# S7G7_footprint_simplified_w_ethernet_Pow.net
KiCad netlist of a schematic drawn in EAGLE
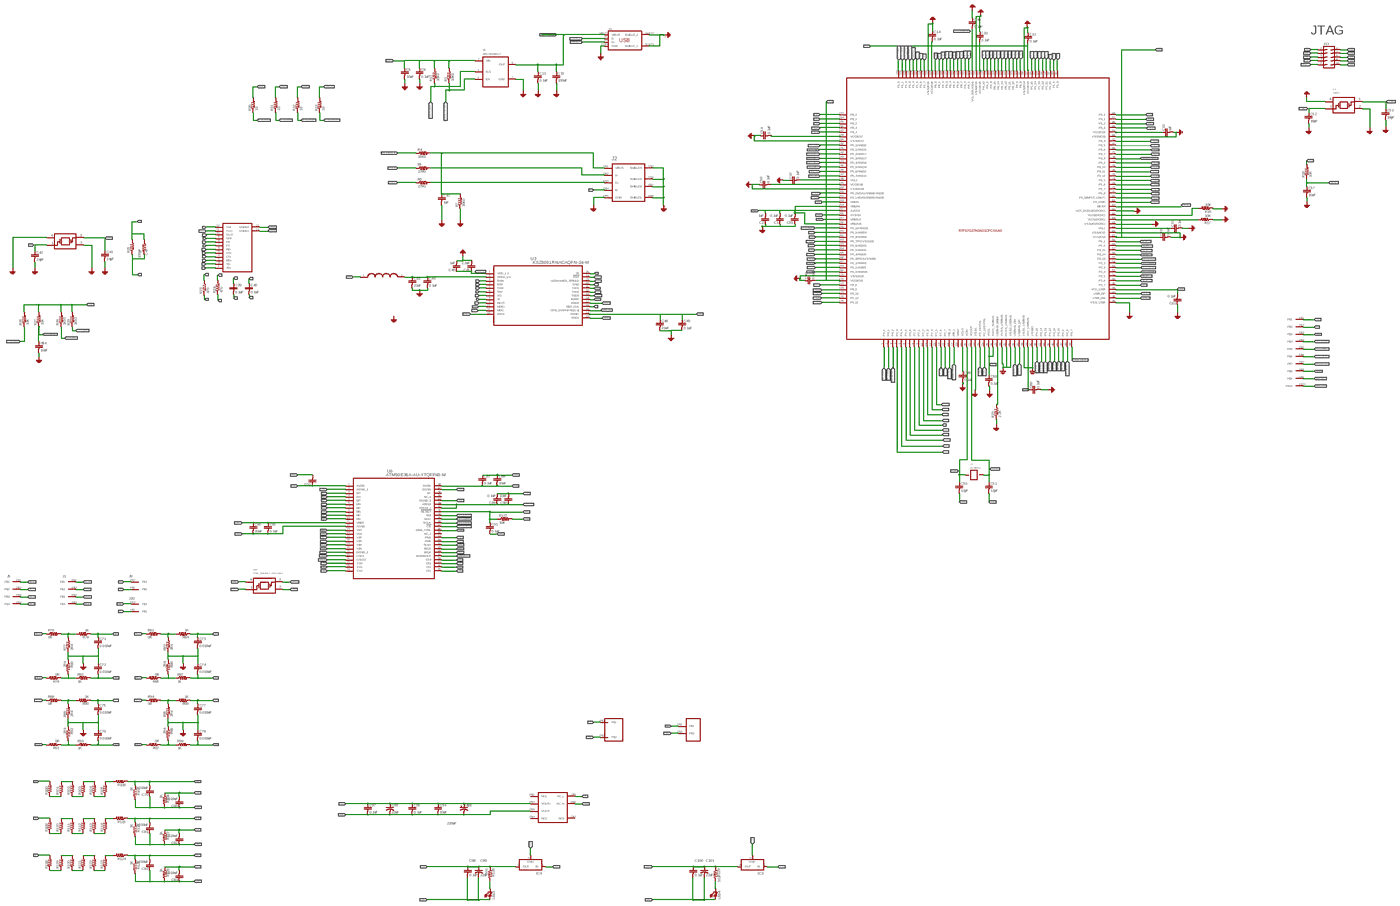
[diagram p0: schematic, sheet 1, overview]
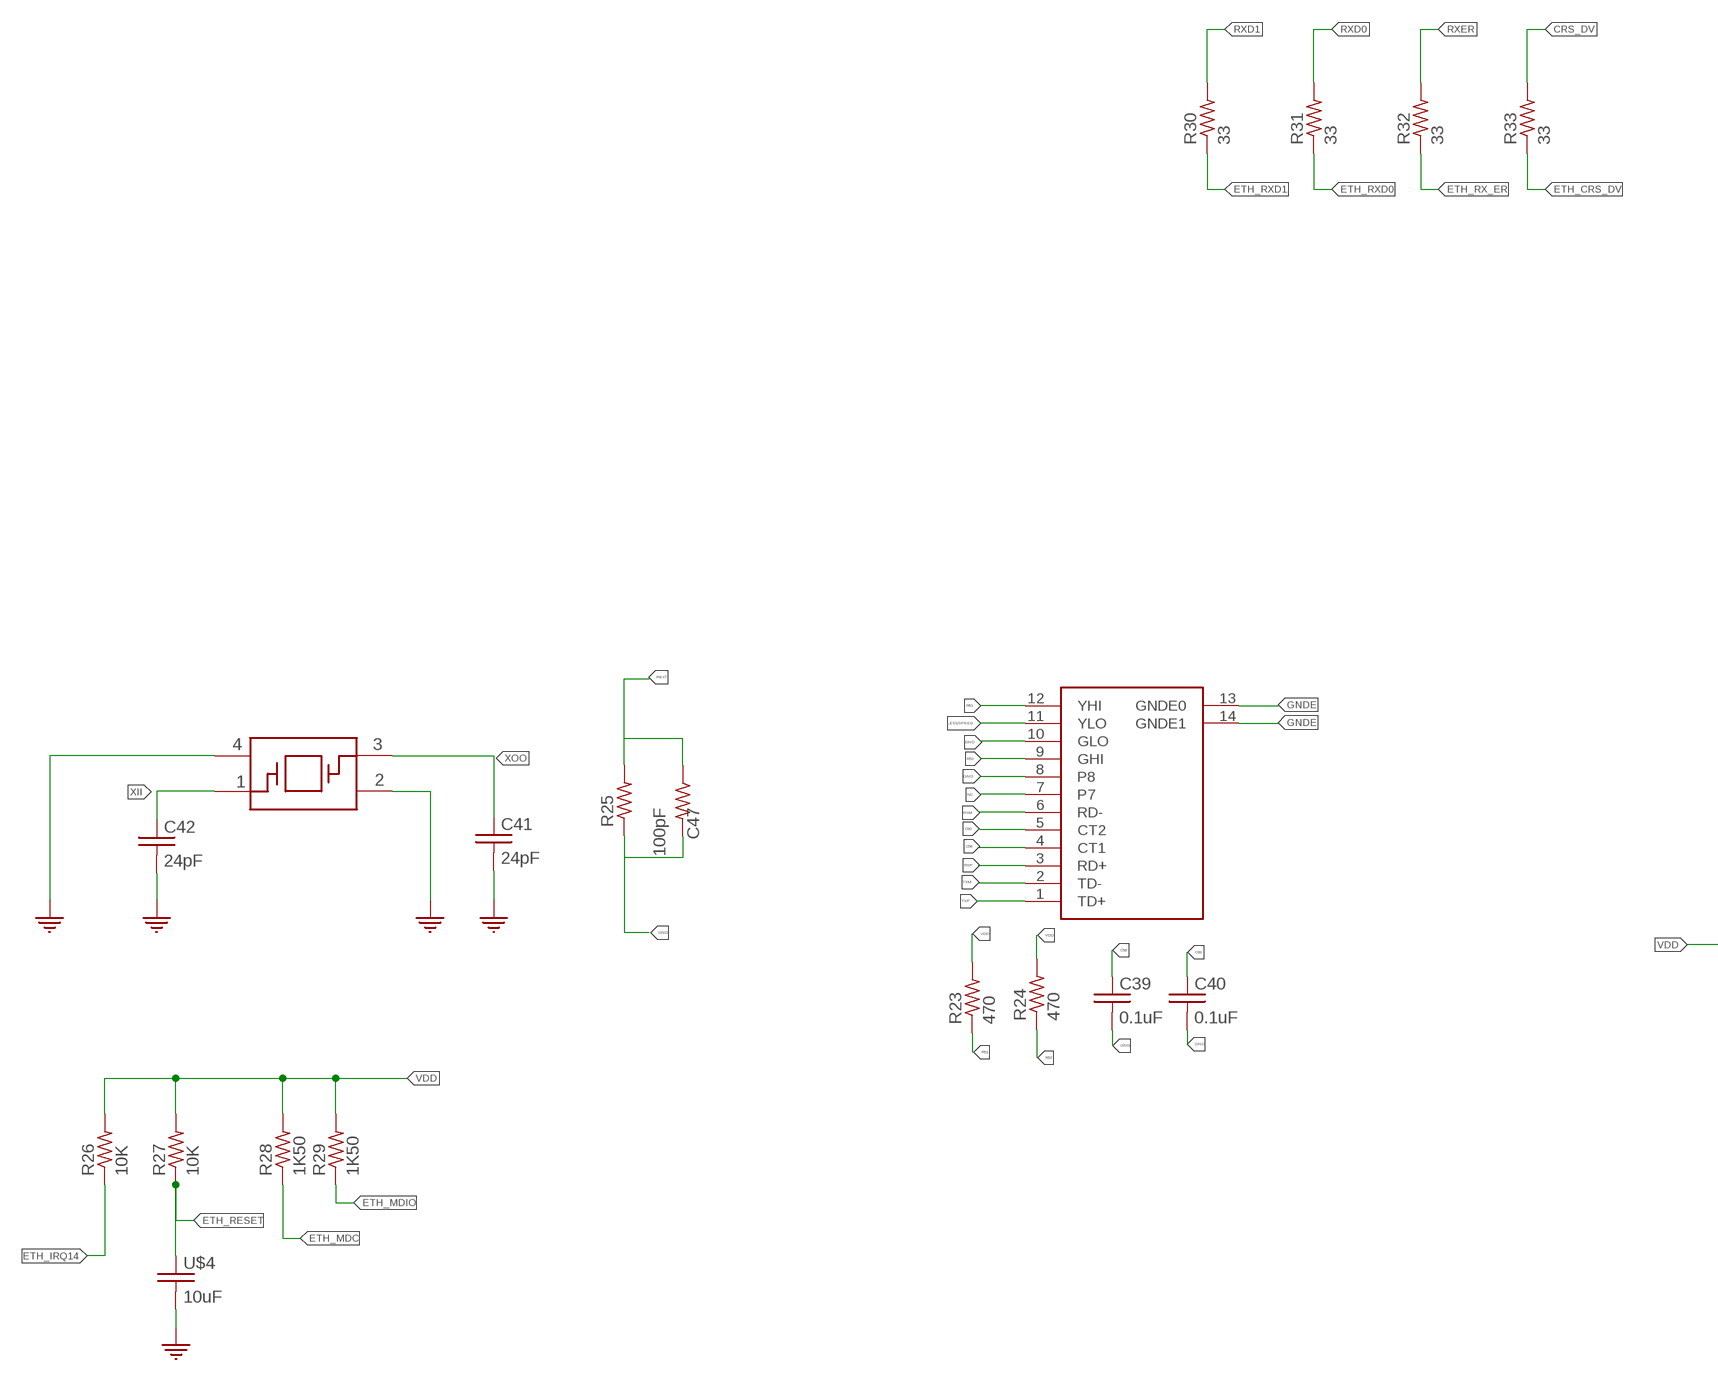
[diagram p1: schematic, sheet 1, part 1 of 6]
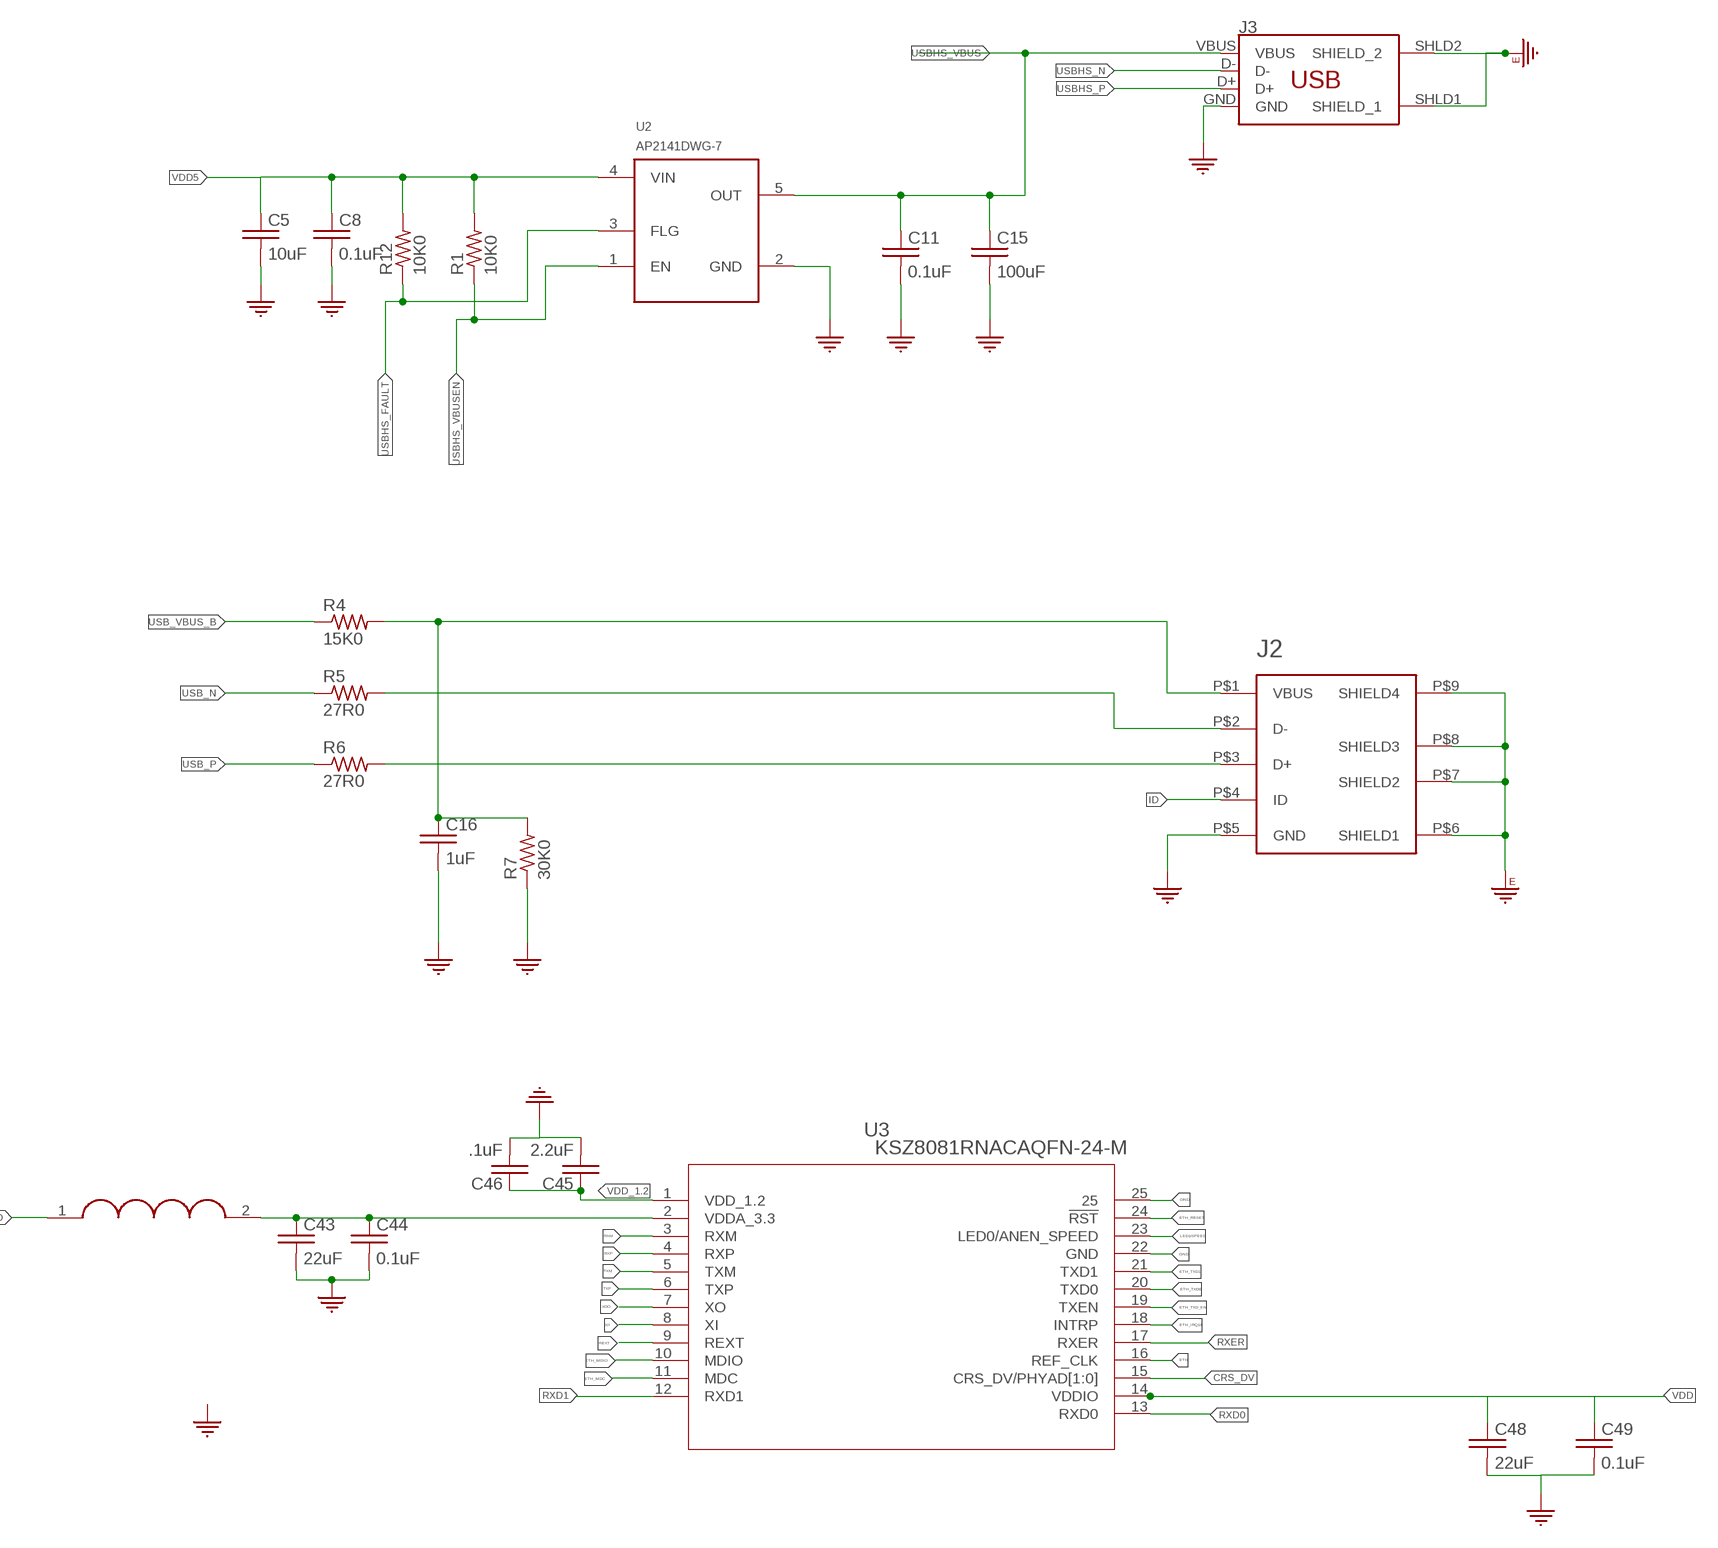
[diagram p2: schematic, sheet 1, part 2 of 6]
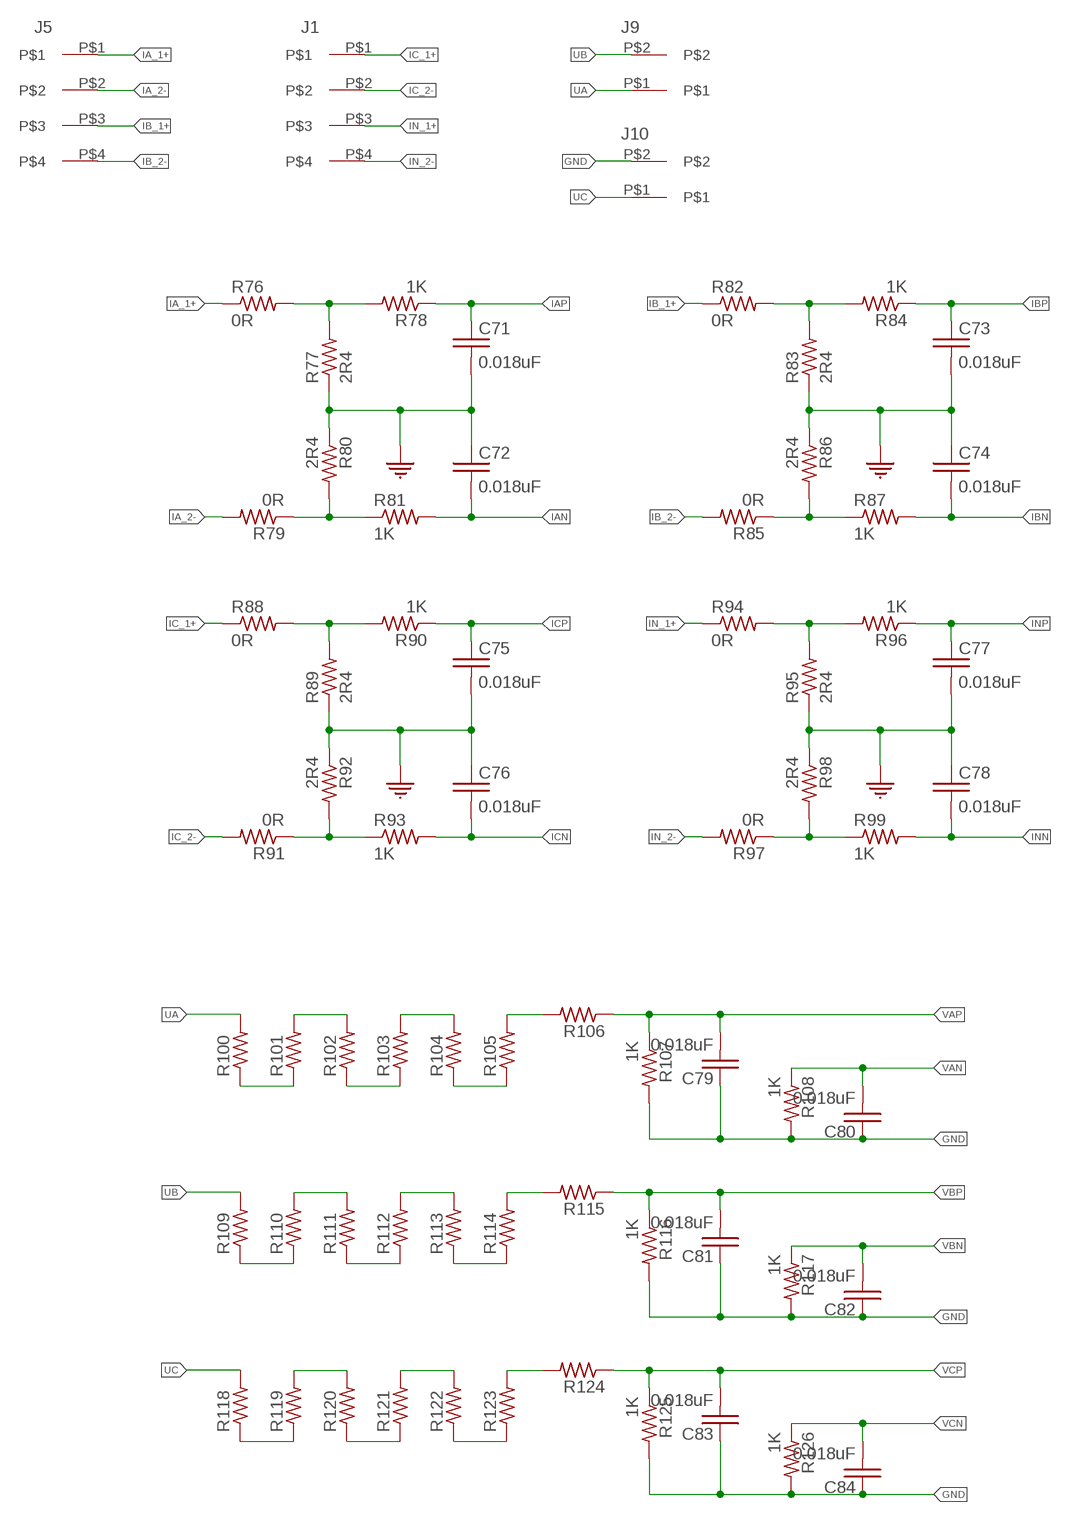
[diagram p3: schematic, sheet 1, part 3 of 6]
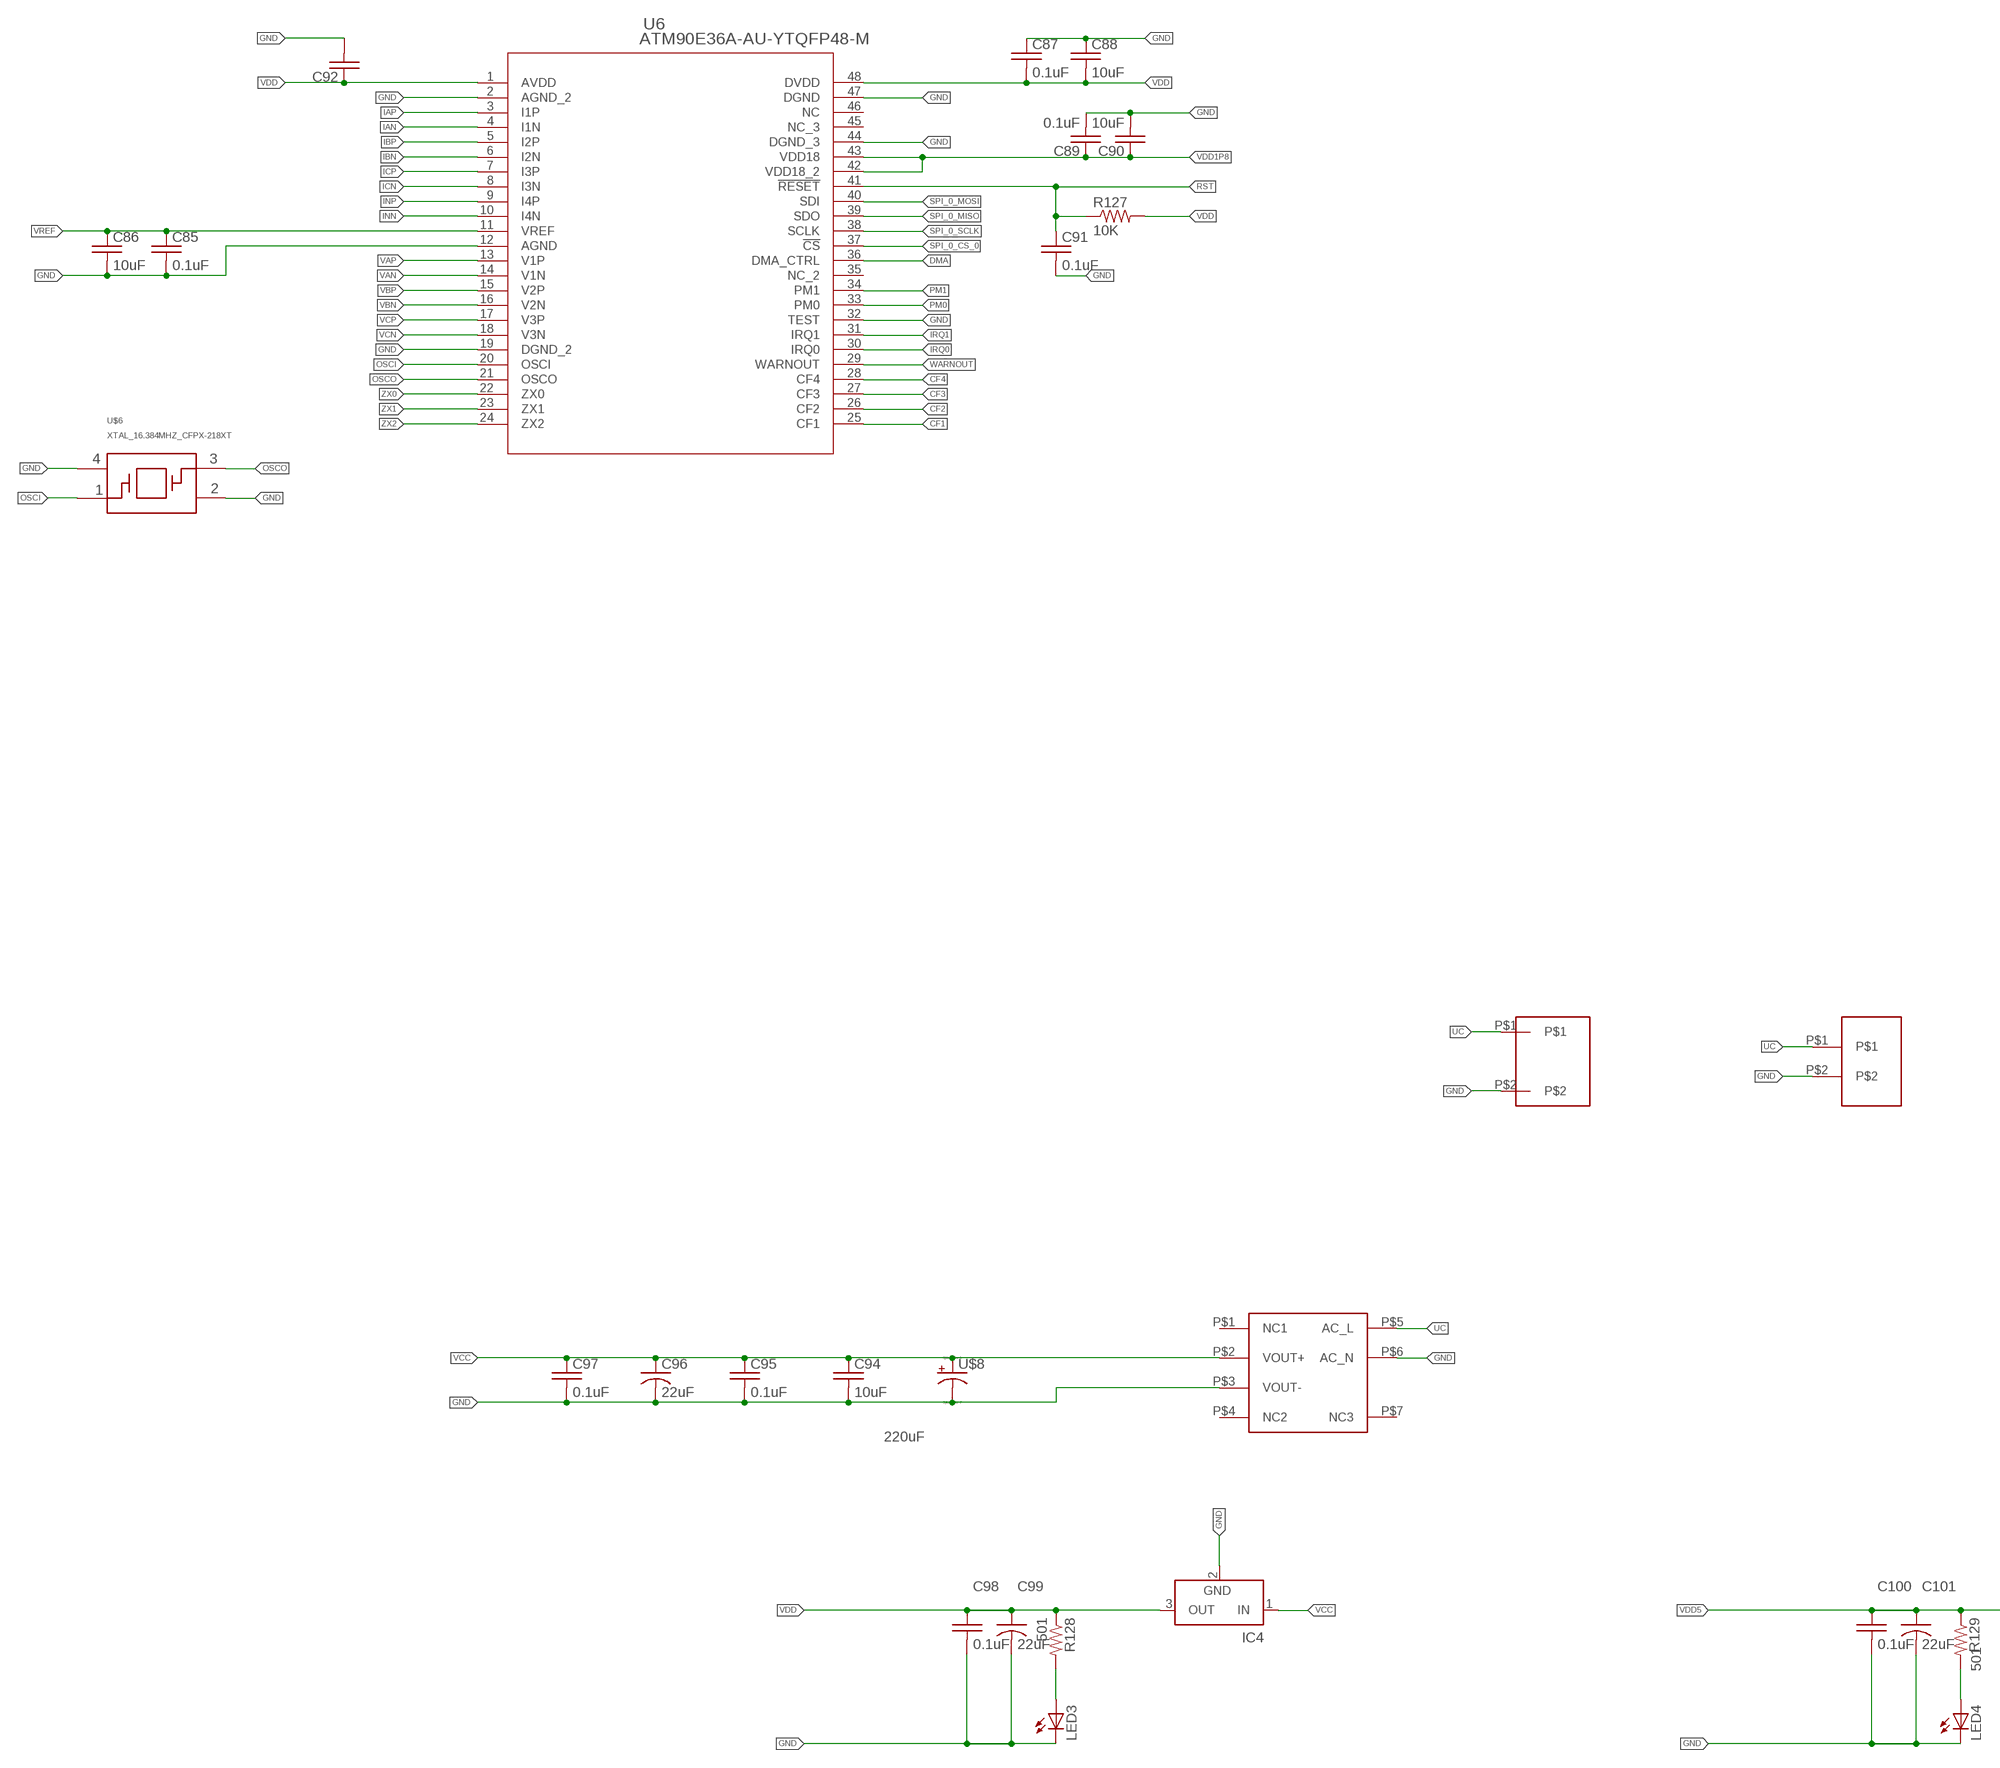
[diagram p4: schematic, sheet 1, part 4 of 6]
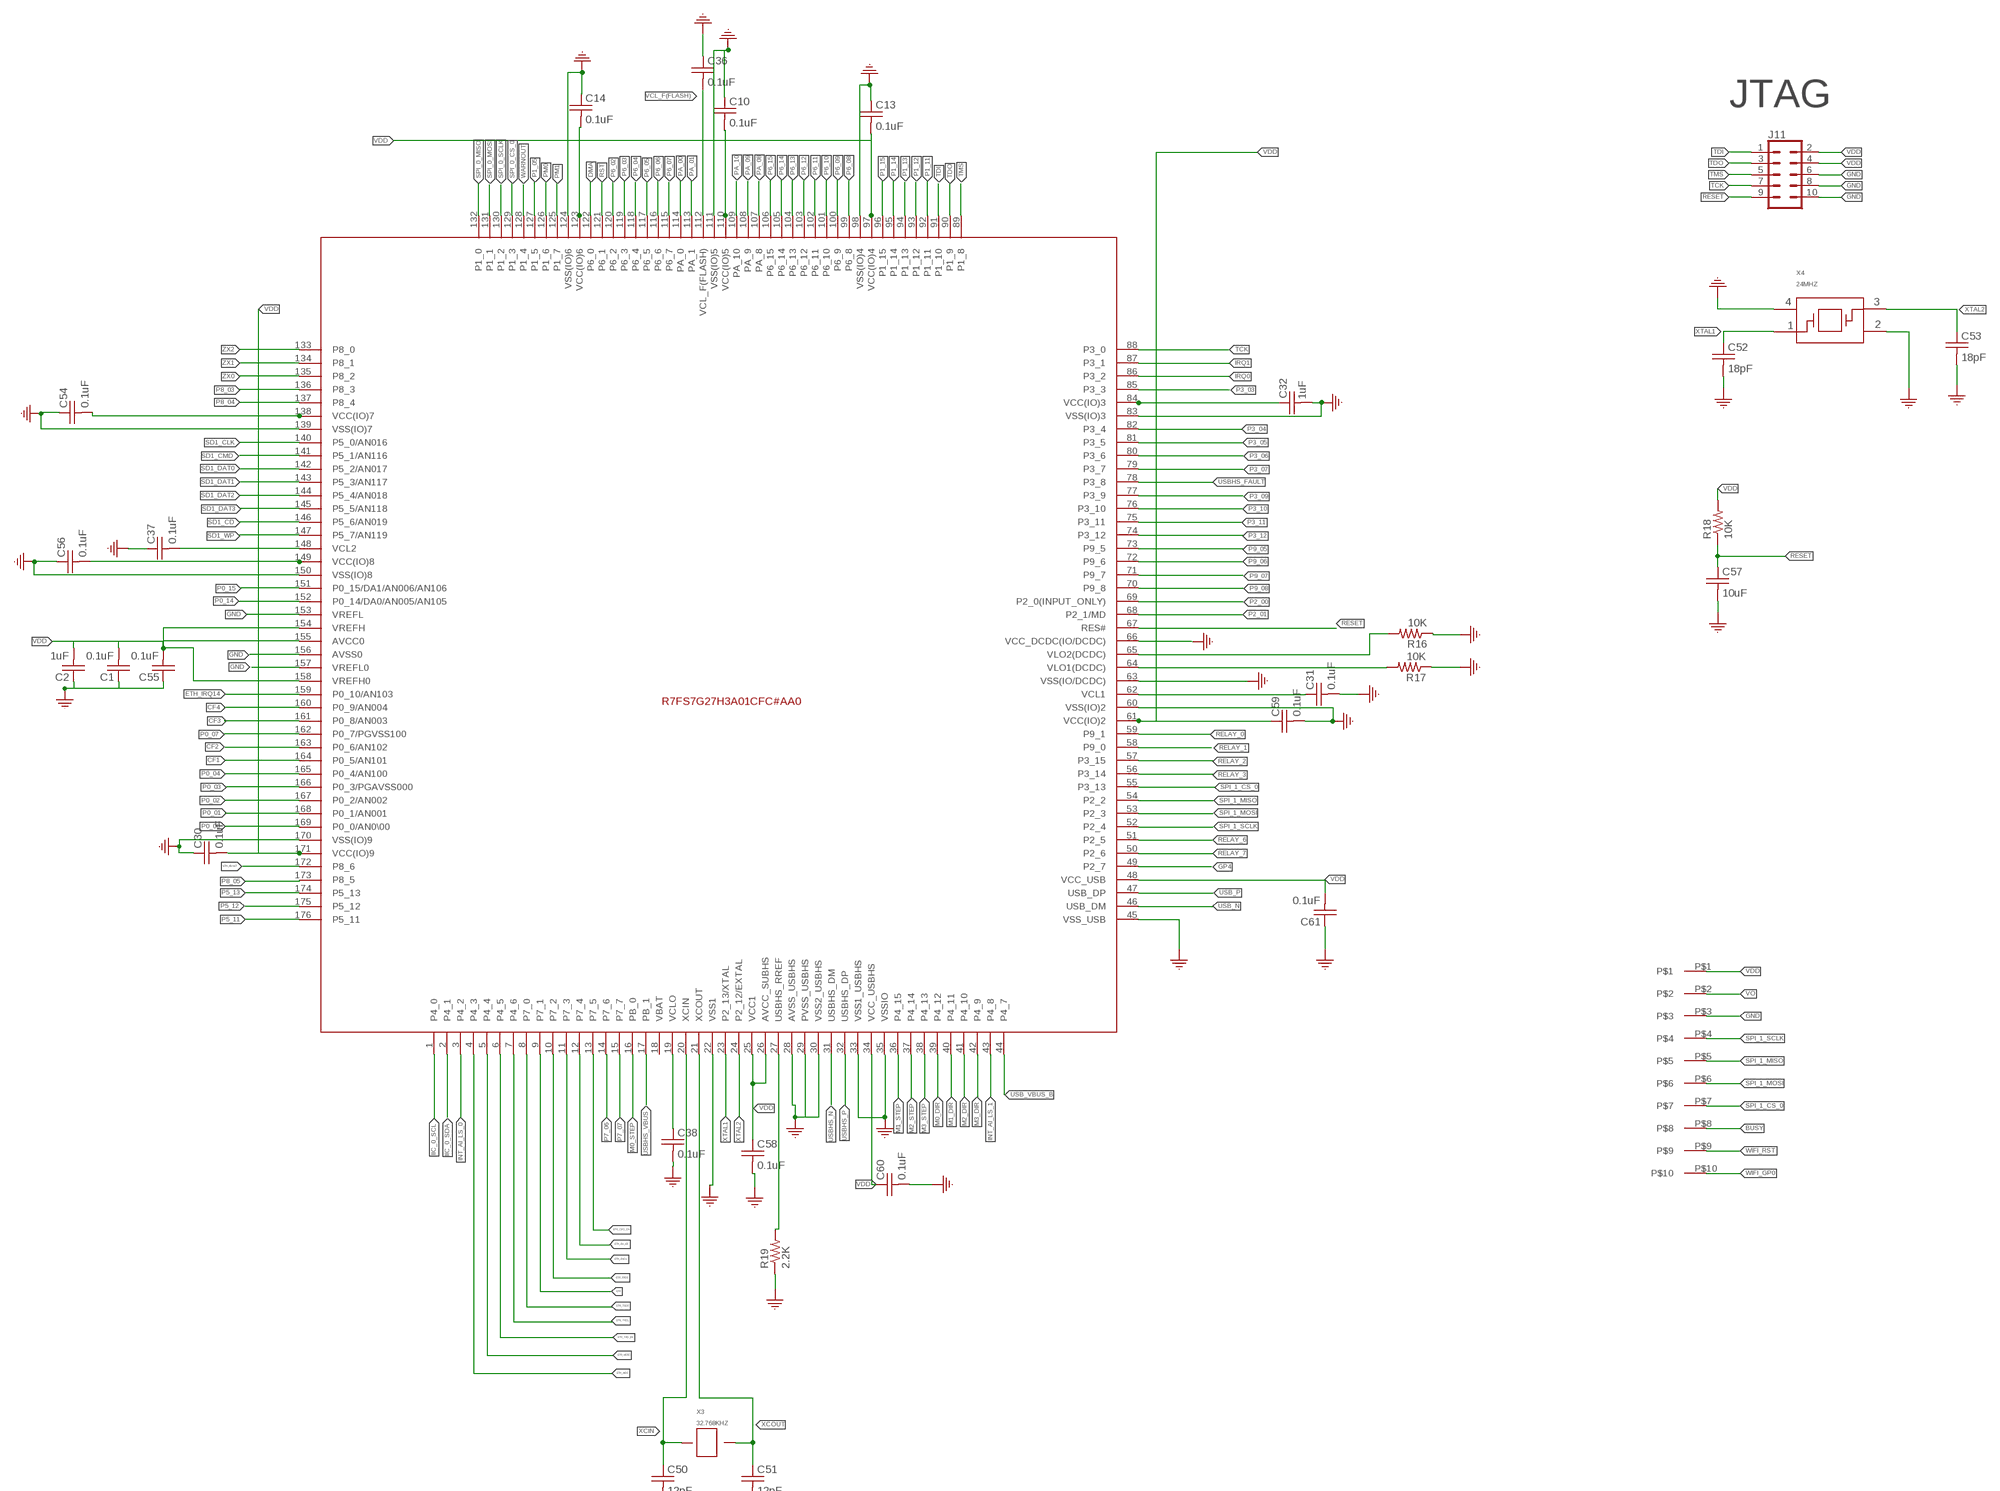
[diagram p5: schematic, sheet 1, part 5 of 6]
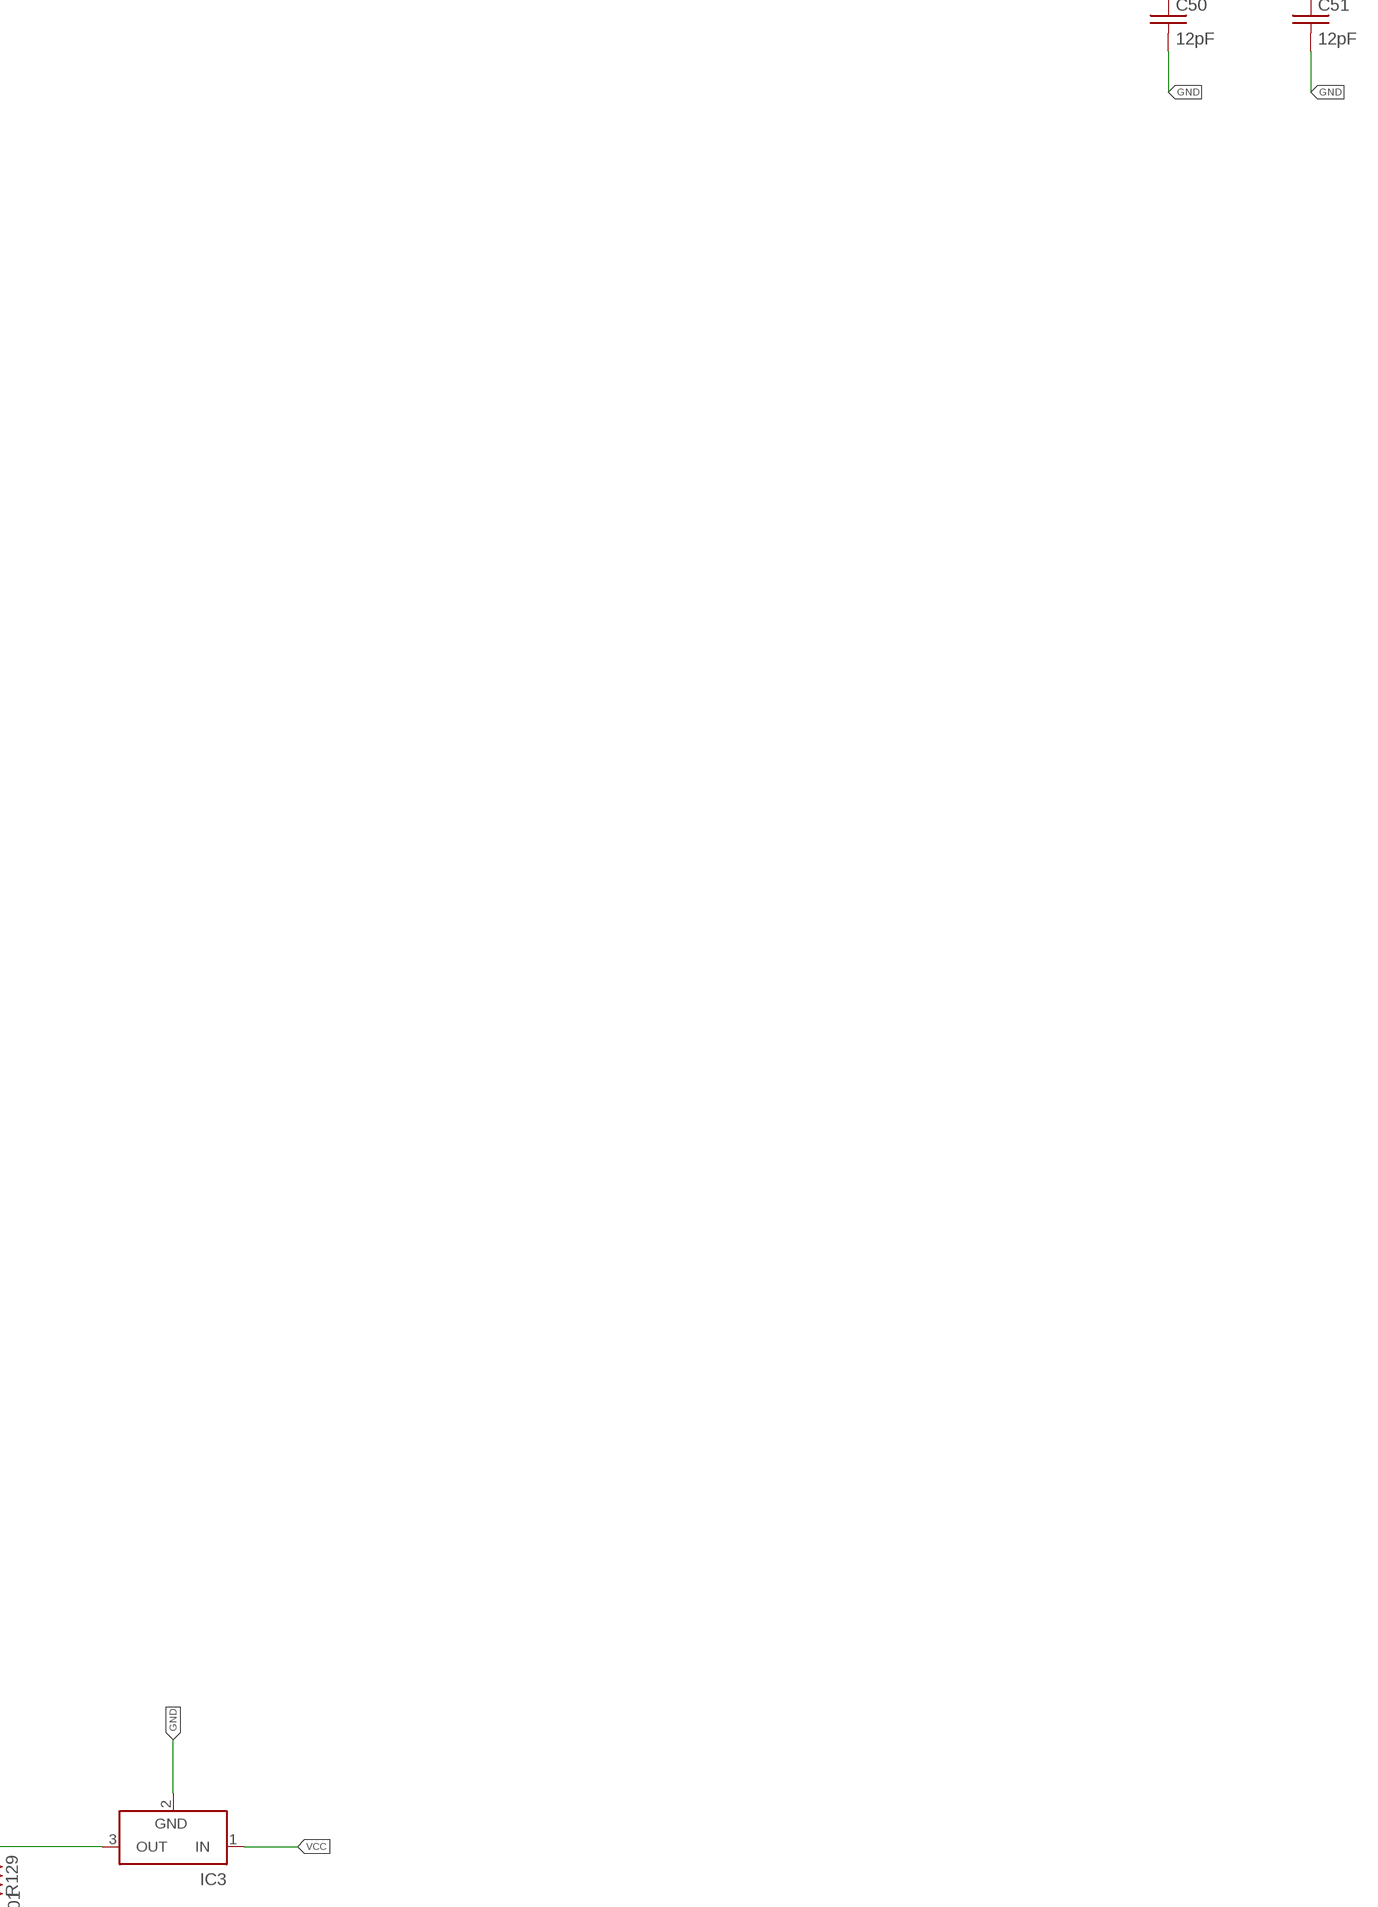
[diagram p6: schematic, sheet 1, part 6 of 6]

(export (version "E")
  (design (tool "Eeschema 10.0.6"))
  (components
    (comp (ref "C1")
      (value "0.1uF")
      (footprint "eagle-import:0402")
      (libsource (lib "eagle-import") (part "C_0402"))
    )
    (comp (ref "C2")
      (value "1uF")
      (footprint "eagle-import:0402")
      (libsource (lib "eagle-import") (part "C_0402"))
    )
    (comp (ref "C5")
      (value "10uF")
      (footprint "eagle-import:0402")
      (libsource (lib "eagle-import") (part "C_0402"))
    )
    (comp (ref "C8")
      (value "0.1uF")
      (footprint "eagle-import:0402")
      (libsource (lib "eagle-import") (part "C_0402"))
    )
    (comp (ref "C10")
      (value "0.1uF")
      (footprint "eagle-import:0402")
      (libsource (lib "eagle-import") (part "C_0402"))
    )
    (comp (ref "C11")
      (value "0.1uF")
      (footprint "eagle-import:0402")
      (libsource (lib "eagle-import") (part "C_0402"))
    )
    (comp (ref "C13")
      (value "0.1uF")
      (footprint "eagle-import:0402")
      (libsource (lib "eagle-import") (part "C_0402"))
    )
    (comp (ref "C14")
      (value "0.1uF")
      (footprint "eagle-import:0402")
      (libsource (lib "eagle-import") (part "C_0402"))
    )
    (comp (ref "C15")
      (value "100uF")
      (footprint "eagle-import:C1210")
      (libsource (lib "eagle-import") (part "C_1210"))
    )
    (comp (ref "C16")
      (value "1uF")
      (footprint "eagle-import:0402")
      (libsource (lib "eagle-import") (part "C_0402"))
    )
    (comp (ref "C30")
      (value "0.1uF")
      (footprint "eagle-import:0402")
      (libsource (lib "eagle-import") (part "C_0402"))
    )
    (comp (ref "C31")
      (value "0.1uF")
      (footprint "eagle-import:0402")
      (libsource (lib "eagle-import") (part "C_0402"))
    )
    (comp (ref "C32")
      (value "1uF")
      (footprint "eagle-import:0402")
      (libsource (lib "eagle-import") (part "C_0402"))
    )
    (comp (ref "C36")
      (value "0.1uF")
      (footprint "eagle-import:0402")
      (libsource (lib "eagle-import") (part "C_0402"))
    )
    (comp (ref "C37")
      (value "0.1uF")
      (footprint "eagle-import:0402")
      (libsource (lib "eagle-import") (part "C_0402"))
    )
    (comp (ref "C38")
      (value "0.1uF")
      (footprint "eagle-import:0402")
      (libsource (lib "eagle-import") (part "C_0402"))
    )
    (comp (ref "C39")
      (value "0.1uF")
      (footprint "eagle-import:0402")
      (libsource (lib "eagle-import") (part "C_0402"))
    )
    (comp (ref "C40")
      (value "0.1uF")
      (footprint "eagle-import:0402")
      (libsource (lib "eagle-import") (part "C_0402"))
    )
    (comp (ref "C41")
      (value "24pF")
      (footprint "eagle-import:0402")
      (libsource (lib "eagle-import") (part "C_0402"))
    )
    (comp (ref "C42")
      (value "24pF")
      (footprint "eagle-import:0402")
      (libsource (lib "eagle-import") (part "C_0402"))
    )
    (comp (ref "C43")
      (value "22uF")
      (footprint "eagle-import:0603")
      (libsource (lib "eagle-import") (part "C_0603"))
    )
    (comp (ref "C44")
      (value "0.1uF")
      (footprint "eagle-import:0402")
      (libsource (lib "eagle-import") (part "C_0402"))
    )
    (comp (ref "C45")
      (value "2.2uF")
      (footprint "eagle-import:0402")
      (libsource (lib "eagle-import") (part "C_0402"))
    )
    (comp (ref "C46")
      (value ".1uF")
      (footprint "eagle-import:0402")
      (libsource (lib "eagle-import") (part "C_0402"))
    )
    (comp (ref "C47")
      (value "100pF")
      (footprint "eagle-import:0402")
      (libsource (lib "eagle-import") (part "R_0402"))
    )
    (comp (ref "C48")
      (value "22uF")
      (footprint "eagle-import:0603")
      (libsource (lib "eagle-import") (part "C_0603"))
    )
    (comp (ref "C49")
      (value "0.1uF")
      (footprint "eagle-import:0402")
      (libsource (lib "eagle-import") (part "C_0402"))
    )
    (comp (ref "C50")
      (value "12pF")
      (footprint "eagle-import:0402")
      (libsource (lib "eagle-import") (part "C_0402"))
    )
    (comp (ref "C51")
      (value "12pF")
      (footprint "eagle-import:0402")
      (libsource (lib "eagle-import") (part "C_0402"))
    )
    (comp (ref "C52")
      (value "18pF")
      (footprint "eagle-import:0402")
      (libsource (lib "eagle-import") (part "C_0402"))
    )
    (comp (ref "C53")
      (value "18pF")
      (footprint "eagle-import:0402")
      (libsource (lib "eagle-import") (part "C_0402"))
    )
    (comp (ref "C54")
      (value "0.1uF")
      (footprint "eagle-import:0402")
      (libsource (lib "eagle-import") (part "C_0402"))
    )
    (comp (ref "C55")
      (value "0.1uF")
      (footprint "eagle-import:0402")
      (libsource (lib "eagle-import") (part "C_0402"))
    )
    (comp (ref "C56")
      (value "0.1uF")
      (footprint "eagle-import:0402")
      (libsource (lib "eagle-import") (part "C_0402"))
    )
    (comp (ref "C57")
      (value "10uF")
      (footprint "eagle-import:0402")
      (libsource (lib "eagle-import") (part "C_0402"))
    )
    (comp (ref "C58")
      (value "0.1uF")
      (footprint "eagle-import:0402")
      (libsource (lib "eagle-import") (part "C_0402"))
    )
    (comp (ref "C59")
      (value "0.1uF")
      (footprint "eagle-import:0402")
      (libsource (lib "eagle-import") (part "C_0402"))
    )
    (comp (ref "C60")
      (value "0.1uF")
      (footprint "eagle-import:0402")
      (libsource (lib "eagle-import") (part "C_0402"))
    )
    (comp (ref "C61")
      (value "0.1uF")
      (footprint "eagle-import:0402")
      (libsource (lib "eagle-import") (part "C_0402"))
    )
    (comp (ref "C71")
      (value "0.018uF")
      (footprint "eagle-import:0402")
      (libsource (lib "eagle-import") (part "C_0402"))
    )
    (comp (ref "C72")
      (value "0.018uF")
      (footprint "eagle-import:0402")
      (libsource (lib "eagle-import") (part "C_0402"))
    )
    (comp (ref "C73")
      (value "0.018uF")
      (footprint "eagle-import:0402")
      (libsource (lib "eagle-import") (part "C_0402"))
    )
    (comp (ref "C74")
      (value "0.018uF")
      (footprint "eagle-import:0402")
      (libsource (lib "eagle-import") (part "C_0402"))
    )
    (comp (ref "C75")
      (value "0.018uF")
      (footprint "eagle-import:0402")
      (libsource (lib "eagle-import") (part "C_0402"))
    )
    (comp (ref "C76")
      (value "0.018uF")
      (footprint "eagle-import:0402")
      (libsource (lib "eagle-import") (part "C_0402"))
    )
    (comp (ref "C77")
      (value "0.018uF")
      (footprint "eagle-import:0402")
      (libsource (lib "eagle-import") (part "C_0402"))
    )
    (comp (ref "C78")
      (value "0.018uF")
      (footprint "eagle-import:0402")
      (libsource (lib "eagle-import") (part "C_0402"))
    )
    (comp (ref "C79")
      (value "0.018uF")
      (footprint "eagle-import:0402")
      (libsource (lib "eagle-import") (part "C_0402"))
    )
    (comp (ref "C80")
      (value "0.018uF")
      (footprint "eagle-import:0402")
      (libsource (lib "eagle-import") (part "C_0402"))
    )
    (comp (ref "C81")
      (value "0.018uF")
      (footprint "eagle-import:0402")
      (libsource (lib "eagle-import") (part "C_0402"))
    )
    (comp (ref "C82")
      (value "0.018uF")
      (footprint "eagle-import:0402")
      (libsource (lib "eagle-import") (part "C_0402"))
    )
    (comp (ref "C83")
      (value "0.018uF")
      (footprint "eagle-import:0402")
      (libsource (lib "eagle-import") (part "C_0402"))
    )
    (comp (ref "C84")
      (value "0.018uF")
      (footprint "eagle-import:0402")
      (libsource (lib "eagle-import") (part "C_0402"))
    )
    (comp (ref "C85")
      (value "0.1uF")
      (footprint "eagle-import:0402")
      (libsource (lib "eagle-import") (part "C_0402"))
    )
    (comp (ref "C86")
      (value "10uF")
      (footprint "eagle-import:0402")
      (libsource (lib "eagle-import") (part "C_0402"))
    )
    (comp (ref "C87")
      (value "0.1uF")
      (footprint "eagle-import:0402")
      (libsource (lib "eagle-import") (part "C_0402"))
    )
    (comp (ref "C88")
      (value "10uF")
      (footprint "eagle-import:0402")
      (libsource (lib "eagle-import") (part "C_0402"))
    )
    (comp (ref "C89")
      (value "0.1uF")
      (footprint "eagle-import:0402")
      (libsource (lib "eagle-import") (part "C_0402"))
    )
    (comp (ref "C90")
      (value "10uF")
      (footprint "eagle-import:0402")
      (libsource (lib "eagle-import") (part "C_0402"))
    )
    (comp (ref "C91")
      (value "0.1uF")
      (footprint "eagle-import:0402")
      (libsource (lib "eagle-import") (part "C_0402"))
    )
    (comp (ref "C92")
      (value "C_0402")
      (footprint "eagle-import:0402")
      (libsource (lib "eagle-import") (part "C_0402"))
    )
    (comp (ref "C93")
      (value "CAP_THIN_FILM_TDK_32922CAP")
      (footprint "eagle-import:CAP_THIN_FILM_32922")
      (libsource (lib "eagle-import") (part "CAP_THIN_FILM_TDK_32922CAP"))
    )
    (comp (ref "C94")
      (value "10uF")
      (footprint "eagle-import:0402")
      (libsource (lib "eagle-import") (part "C_0402"))
    )
    (comp (ref "C95")
      (value "0.1uF")
      (footprint "eagle-import:0402")
      (libsource (lib "eagle-import") (part "C_0402"))
    )
    (comp (ref "C96")
      (value "22uF")
      (footprint "eagle-import:C1206")
      (libsource (lib "eagle-import") (part "C-USC1206"))
    )
    (comp (ref "C97")
      (value "0.1uF")
      (footprint "eagle-import:0402")
      (libsource (lib "eagle-import") (part "C_0402"))
    )
    (comp (ref "C98")
      (value "0.1uF")
      (footprint "eagle-import:0402")
      (libsource (lib "eagle-import") (part "C_0402"))
    )
    (comp (ref "C99")
      (value "22uF")
      (footprint "eagle-import:C1206")
      (libsource (lib "eagle-import") (part "C-USC1206"))
    )
    (comp (ref "C100")
      (value "0.1uF")
      (footprint "eagle-import:0402")
      (libsource (lib "eagle-import") (part "C_0402"))
    )
    (comp (ref "C101")
      (value "22uF")
      (footprint "eagle-import:C1206")
      (libsource (lib "eagle-import") (part "C-USC1206"))
    )
    (comp (ref "FB2/2")
      (value "FB_0805_120_OHM")
      (footprint "eagle-import:0805")
      (libsource (lib "eagle-import") (part "FB_0805_120_OHM"))
    )
    (comp (ref "IC3")
      (value "LT1129CST5")
      (footprint "eagle-import:SOT223")
      (fields (field (name "MPN") "LT1129CST-5#PBF"))
      (libsource (lib "eagle-import") (part "LT1129CST5"))
    )
    (comp (ref "IC4")
      (value "LT1129CST3")
      (footprint "eagle-import:SOT223")
      (fields (field (name "MPN") "LT1129CST-5#PBF"))
      (libsource (lib "eagle-import") (part "LT1129CST3"))
    )
    (comp (ref "J1")
      (value "3.81MM_1_X_4_RT_ANGLE_PLUG_HEADER")
      (footprint "eagle-import:1X4_3.81MM_PITCH")
      (libsource (lib "eagle-import") (part "3.81MM_1_X_4_RT_ANGLE_PLUG_HEADER"))
    )
    (comp (ref "J2")
      (value "USB_MICRO-B")
      (footprint "eagle-import:USB_MICRO-B")
      (libsource (lib "eagle-import") (part "USB_MICRO-B"))
    )
    (comp (ref "J3")
      (value "USB_A")
      (footprint "eagle-import:USB_A_SMT")
      (libsource (lib "eagle-import") (part "USB_A"))
    )
    (comp (ref "J4")
      (value "RJ45_WITH_ELEC")
      (footprint "eagle-import:RJ45_TH_ELEC")
      (libsource (lib "eagle-import") (part "RJ45_WITH_ELEC"))
    )
    (comp (ref "J5")
      (value "3.81MM_1_X_4_RT_ANGLE_PLUG_HEADER")
      (footprint "eagle-import:1X4_3.81MM_PITCH")
      (libsource (lib "eagle-import") (part "3.81MM_1_X_4_RT_ANGLE_PLUG_HEADER"))
    )
    (comp (ref "J9")
      (value "3.81MM_1_X_2_RT_ANGLE_PLUG_HEADER")
      (footprint "eagle-import:2_3.81MM_PITCH")
      (libsource (lib "eagle-import") (part "3.81MM_1_X_2_RT_ANGLE_PLUG_HEADER"))
    )
    (comp (ref "J10")
      (value "3.81MM_1_X_2_RT_ANGLE_PLUG_HEADER")
      (footprint "eagle-import:2_3.81MM_PITCH")
      (libsource (lib "eagle-import") (part "3.81MM_1_X_2_RT_ANGLE_PLUG_HEADER"))
    )
    (comp (ref "J11")
      (value "CONN_05X2PTH")
      (footprint "eagle-import:2X5")
      (libsource (lib "eagle-import") (part "CONN_05X2PTH"))
    )
    (comp (ref "LED3")
      (value "LED_0805_GREEN")
      (footprint "eagle-import:LED_0805_GREEN")
      (libsource (lib "eagle-import") (part "LED_0805_GREEN"))
    )
    (comp (ref "LED4")
      (value "LED_0805_GREEN")
      (footprint "eagle-import:LED_0805_GREEN")
      (libsource (lib "eagle-import") (part "LED_0805_GREEN"))
    )
    (comp (ref "R1")
      (value "10K0")
      (footprint "eagle-import:0402")
      (libsource (lib "eagle-import") (part "R_0402"))
    )
    (comp (ref "R4")
      (value "15K0")
      (footprint "eagle-import:0402")
      (libsource (lib "eagle-import") (part "R_0402"))
    )
    (comp (ref "R5")
      (value "27R0")
      (footprint "eagle-import:0402")
      (libsource (lib "eagle-import") (part "R_0402"))
    )
    (comp (ref "R6")
      (value "27R0")
      (footprint "eagle-import:0402")
      (libsource (lib "eagle-import") (part "R_0402"))
    )
    (comp (ref "R7")
      (value "30K0")
      (footprint "eagle-import:0402")
      (libsource (lib "eagle-import") (part "R_0402"))
    )
    (comp (ref "R12")
      (value "10K0")
      (footprint "eagle-import:0402")
      (libsource (lib "eagle-import") (part "R_0402"))
    )
    (comp (ref "R16")
      (value "10K")
      (footprint "eagle-import:0402")
      (libsource (lib "eagle-import") (part "R_0402"))
    )
    (comp (ref "R17")
      (value "10K")
      (footprint "eagle-import:0402")
      (libsource (lib "eagle-import") (part "R_0402"))
    )
    (comp (ref "R18")
      (value "10K")
      (footprint "eagle-import:0402")
      (libsource (lib "eagle-import") (part "R_0402"))
    )
    (comp (ref "R19")
      (value "2.2K")
      (footprint "eagle-import:0402")
      (libsource (lib "eagle-import") (part "R_0402"))
    )
    (comp (ref "R23")
      (value "470")
      (footprint "eagle-import:0402")
      (libsource (lib "eagle-import") (part "R_0402"))
    )
    (comp (ref "R24")
      (value "470")
      (footprint "eagle-import:0402")
      (libsource (lib "eagle-import") (part "R_0402"))
    )
    (comp (ref "R25")
      (value "6k49")
      (footprint "eagle-import:0402")
      (libsource (lib "eagle-import") (part "R_0402"))
    )
    (comp (ref "R26")
      (value "10K")
      (footprint "eagle-import:0402")
      (libsource (lib "eagle-import") (part "R_0402"))
    )
    (comp (ref "R27")
      (value "10K")
      (footprint "eagle-import:0402")
      (libsource (lib "eagle-import") (part "R_0402"))
    )
    (comp (ref "R28")
      (value "1K50")
      (footprint "eagle-import:0402")
      (libsource (lib "eagle-import") (part "R_0402"))
    )
    (comp (ref "R29")
      (value "1K50")
      (footprint "eagle-import:0402")
      (libsource (lib "eagle-import") (part "R_0402"))
    )
    (comp (ref "R30")
      (value "33")
      (footprint "eagle-import:0402")
      (libsource (lib "eagle-import") (part "R_0402"))
    )
    (comp (ref "R31")
      (value "33")
      (footprint "eagle-import:0402")
      (libsource (lib "eagle-import") (part "R_0402"))
    )
    (comp (ref "R32")
      (value "33")
      (footprint "eagle-import:0402")
      (libsource (lib "eagle-import") (part "R_0402"))
    )
    (comp (ref "R33")
      (value "33")
      (footprint "eagle-import:0402")
      (libsource (lib "eagle-import") (part "R_0402"))
    )
    (comp (ref "R76")
      (value "0R")
      (footprint "eagle-import:0402")
      (libsource (lib "eagle-import") (part "R_0402"))
    )
    (comp (ref "R77")
      (value "2R4")
      (footprint "eagle-import:0402")
      (libsource (lib "eagle-import") (part "R_0402"))
    )
    (comp (ref "R78")
      (value "1K")
      (footprint "eagle-import:0402")
      (libsource (lib "eagle-import") (part "R_0402"))
    )
    (comp (ref "R79")
      (value "0R")
      (footprint "eagle-import:0402")
      (libsource (lib "eagle-import") (part "R_0402"))
    )
    (comp (ref "R80")
      (value "2R4")
      (footprint "eagle-import:0402")
      (libsource (lib "eagle-import") (part "R_0402"))
    )
    (comp (ref "R81")
      (value "1K")
      (footprint "eagle-import:0402")
      (libsource (lib "eagle-import") (part "R_0402"))
    )
    (comp (ref "R82")
      (value "0R")
      (footprint "eagle-import:0402")
      (libsource (lib "eagle-import") (part "R_0402"))
    )
    (comp (ref "R83")
      (value "2R4")
      (footprint "eagle-import:0402")
      (libsource (lib "eagle-import") (part "R_0402"))
    )
    (comp (ref "R84")
      (value "1K")
      (footprint "eagle-import:0402")
      (libsource (lib "eagle-import") (part "R_0402"))
    )
    (comp (ref "R85")
      (value "0R")
      (footprint "eagle-import:0402")
      (libsource (lib "eagle-import") (part "R_0402"))
    )
    (comp (ref "R86")
      (value "2R4")
      (footprint "eagle-import:0402")
      (libsource (lib "eagle-import") (part "R_0402"))
    )
    (comp (ref "R87")
      (value "1K")
      (footprint "eagle-import:0402")
      (libsource (lib "eagle-import") (part "R_0402"))
    )
    (comp (ref "R88")
      (value "0R")
      (footprint "eagle-import:0402")
      (libsource (lib "eagle-import") (part "R_0402"))
    )
    (comp (ref "R89")
      (value "2R4")
      (footprint "eagle-import:0402")
      (libsource (lib "eagle-import") (part "R_0402"))
    )
    (comp (ref "R90")
      (value "1K")
      (footprint "eagle-import:0402")
      (libsource (lib "eagle-import") (part "R_0402"))
    )
    (comp (ref "R91")
      (value "0R")
      (footprint "eagle-import:0402")
      (libsource (lib "eagle-import") (part "R_0402"))
    )
    (comp (ref "R92")
      (value "2R4")
      (footprint "eagle-import:0402")
      (libsource (lib "eagle-import") (part "R_0402"))
    )
    (comp (ref "R93")
      (value "1K")
      (footprint "eagle-import:0402")
      (libsource (lib "eagle-import") (part "R_0402"))
    )
    (comp (ref "R94")
      (value "0R")
      (footprint "eagle-import:0402")
      (libsource (lib "eagle-import") (part "R_0402"))
    )
    (comp (ref "R95")
      (value "2R4")
      (footprint "eagle-import:0402")
      (libsource (lib "eagle-import") (part "R_0402"))
    )
    (comp (ref "R96")
      (value "1K")
      (footprint "eagle-import:0402")
      (libsource (lib "eagle-import") (part "R_0402"))
    )
    (comp (ref "R97")
      (value "0R")
      (footprint "eagle-import:0402")
      (libsource (lib "eagle-import") (part "R_0402"))
    )
    (comp (ref "R98")
      (value "2R4")
      (footprint "eagle-import:0402")
      (libsource (lib "eagle-import") (part "R_0402"))
    )
    (comp (ref "R99")
      (value "1K")
      (footprint "eagle-import:0402")
      (libsource (lib "eagle-import") (part "R_0402"))
    )
    (comp (ref "R100")
      (value "R_0402")
      (footprint "eagle-import:0402")
      (libsource (lib "eagle-import") (part "R_0402"))
    )
    (comp (ref "R101")
      (value "R_0402")
      (footprint "eagle-import:0402")
      (libsource (lib "eagle-import") (part "R_0402"))
    )
    (comp (ref "R102")
      (value "R_0402")
      (footprint "eagle-import:0402")
      (libsource (lib "eagle-import") (part "R_0402"))
    )
    (comp (ref "R103")
      (value "R_0402")
      (footprint "eagle-import:0402")
      (libsource (lib "eagle-import") (part "R_0402"))
    )
    (comp (ref "R104")
      (value "R_0402")
      (footprint "eagle-import:0402")
      (libsource (lib "eagle-import") (part "R_0402"))
    )
    (comp (ref "R105")
      (value "R_0402")
      (footprint "eagle-import:0402")
      (libsource (lib "eagle-import") (part "R_0402"))
    )
    (comp (ref "R106")
      (value "R_0402")
      (footprint "eagle-import:0402")
      (libsource (lib "eagle-import") (part "R_0402"))
    )
    (comp (ref "R107")
      (value "1K")
      (footprint "eagle-import:0402")
      (libsource (lib "eagle-import") (part "R_0402"))
    )
    (comp (ref "R108")
      (value "1K")
      (footprint "eagle-import:0402")
      (libsource (lib "eagle-import") (part "R_0402"))
    )
    (comp (ref "R109")
      (value "R_0402")
      (footprint "eagle-import:0402")
      (libsource (lib "eagle-import") (part "R_0402"))
    )
    (comp (ref "R110")
      (value "R_0402")
      (footprint "eagle-import:0402")
      (libsource (lib "eagle-import") (part "R_0402"))
    )
    (comp (ref "R111")
      (value "R_0402")
      (footprint "eagle-import:0402")
      (libsource (lib "eagle-import") (part "R_0402"))
    )
    (comp (ref "R112")
      (value "R_0402")
      (footprint "eagle-import:0402")
      (libsource (lib "eagle-import") (part "R_0402"))
    )
    (comp (ref "R113")
      (value "R_0402")
      (footprint "eagle-import:0402")
      (libsource (lib "eagle-import") (part "R_0402"))
    )
    (comp (ref "R114")
      (value "R_0402")
      (footprint "eagle-import:0402")
      (libsource (lib "eagle-import") (part "R_0402"))
    )
    (comp (ref "R115")
      (value "R_0402")
      (footprint "eagle-import:0402")
      (libsource (lib "eagle-import") (part "R_0402"))
    )
    (comp (ref "R116")
      (value "1K")
      (footprint "eagle-import:0402")
      (libsource (lib "eagle-import") (part "R_0402"))
    )
    (comp (ref "R117")
      (value "1K")
      (footprint "eagle-import:0402")
      (libsource (lib "eagle-import") (part "R_0402"))
    )
    (comp (ref "R118")
      (value "R_0402")
      (footprint "eagle-import:0402")
      (libsource (lib "eagle-import") (part "R_0402"))
    )
    (comp (ref "R119")
      (value "R_0402")
      (footprint "eagle-import:0402")
      (libsource (lib "eagle-import") (part "R_0402"))
    )
    (comp (ref "R120")
      (value "R_0402")
      (footprint "eagle-import:0402")
      (libsource (lib "eagle-import") (part "R_0402"))
    )
    (comp (ref "R121")
      (value "R_0402")
      (footprint "eagle-import:0402")
      (libsource (lib "eagle-import") (part "R_0402"))
    )
    (comp (ref "R122")
      (value "R_0402")
      (footprint "eagle-import:0402")
      (libsource (lib "eagle-import") (part "R_0402"))
    )
    (comp (ref "R123")
      (value "R_0402")
      (footprint "eagle-import:0402")
      (libsource (lib "eagle-import") (part "R_0402"))
    )
    (comp (ref "R124")
      (value "R_0402")
      (footprint "eagle-import:0402")
      (libsource (lib "eagle-import") (part "R_0402"))
    )
    (comp (ref "R125")
      (value "1K")
      (footprint "eagle-import:0402")
      (libsource (lib "eagle-import") (part "R_0402"))
    )
    (comp (ref "R126")
      (value "1K")
      (footprint "eagle-import:0402")
      (libsource (lib "eagle-import") (part "R_0402"))
    )
    (comp (ref "R127")
      (value "10K")
      (footprint "eagle-import:0402")
      (libsource (lib "eagle-import") (part "R_0402"))
    )
    (comp (ref "R128")
      (value "501")
      (footprint "eagle-import:0402")
      (libsource (lib "eagle-import") (part "R_0402"))
    )
    (comp (ref "R129")
      (value "501")
      (footprint "eagle-import:0402")
      (libsource (lib "eagle-import") (part "R_0402"))
    )
    (comp (ref "U$1")
      (value "1_X_10_HEADER_GENERIC_.1INCH")
      (footprint "eagle-import:HEADER_1_X_10_.1_INCH")
      (libsource (lib "eagle-import") (part "1_X_10_HEADER_GENERIC_.1INCH"))
    )
    (comp (ref "U$3")
      (value "XTAL_25_MHZ")
      (footprint "eagle-import:SMD_3225")
      (libsource (lib "eagle-import") (part "XTAL_25_MHZ"))
    )
    (comp (ref "U$4")
      (value "10uF")
      (footprint "eagle-import:0402")
      (libsource (lib "eagle-import") (part "C_0402"))
    )
    (comp (ref "U$6")
      (value "XTAL_16.384MHZ_CFPX-218XT")
      (footprint "eagle-import:XTAL_2.5X2.0")
      (libsource (lib "eagle-import") (part "XTAL_16.384MHZ_CFPX-218XT"))
    )
    (comp (ref "U$7")
      (value "VAR_10MM_VDRUS10")
      (footprint "eagle-import:VAR_10MM_VDRUS10")
      (libsource (lib "eagle-import") (part "VAR_10MM_VDRUS10"))
    )
    (comp (ref "U$8")
      (value "220uF")
      (footprint "eagle-import:C_AL_ELECTROLYTIC_SMD_220UF")
      (libsource (lib "eagle-import") (part "C_AL_ELECTROLYTIC_SMD_220UF"))
    )
    (comp (ref "U2")
      (value "AP2141DWG-5")
      (footprint "eagle-import:SOT-23-5")
      (libsource (lib "eagle-import") (part "AP2141DWG-5"))
    )
    (comp (ref "U3")
      (value "KSZ8081RNACAQFN-24-M")
      (footprint "eagle-import:QFN-24-M")
      (fields (field (name "MANUFACTURER_PART_NUMBER") "KSZ8081RNACA"))
      (libsource (lib "eagle-import") (part "KSZ8081RNACAQFN-24-M"))
    )
    (comp (ref "U4")
      (value "S7G2_X_176")
      (footprint "eagle-import:LQFP176_24X24")
      (libsource (lib "eagle-import") (part "S7G2_X_176"))
    )
    (comp (ref "U6")
      (value "ATM90E36A-AU-YTQFP48-M")
      (footprint "eagle-import:TQFP48-M")
      (fields (field (name "MANUFACTURER_PART_NUMBER") "ATM90E36AAUY"))
      (libsource (lib "eagle-import") (part "ATM90E36A-AU-YTQFP48-M"))
    )
    (comp (ref "U7")
      (value "TMLM_04109")
      (footprint "eagle-import:TMLM04")
      (libsource (lib "eagle-import") (part "TMLM_04109"))
    )
    (comp (ref "X3")
      (value "32.768KHZ")
      (footprint "eagle-import:SMD_X_2_PADS")
      (libsource (lib "eagle-import") (part "XTAL_32.768KHZ"))
    )
    (comp (ref "X4")
      (value "24MHZ")
      (footprint "eagle-import:SMD_3225")
      (libsource (lib "eagle-import") (part "XTAL_24_MHZ"))
    )
  )
  (nets
    (net (code "1") (name "BUSY") (class "Default")
      (node (ref "U$1") (pin "P$8") (pinfunction "P$8_P$8") (pintype "bidirectional"))
    )
    (net (code "2") (name "C58") (class "Default")
      (node (ref "C39") (pin "P$1") (pinfunction "1_P$1") (pintype "passive"))
      (node (ref "J4") (pin "4") (pinfunction "CT1_4") (pintype "bidirectional"))
    )
    (net (code "3") (name "C60") (class "Default")
      (node (ref "C40") (pin "P$1") (pinfunction "1_P$1") (pintype "passive"))
      (node (ref "J4") (pin "5") (pinfunction "CT2_5") (pintype "bidirectional"))
    )
    (net (code "4") (name "CF1") (class "Default")
      (node (ref "U4") (pin "164") (pinfunction "P0_5/AN101_164") (pintype "bidirectional"))
      (node (ref "U6") (pin "25") (pinfunction "CF1_25") (pintype "output"))
    )
    (net (code "5") (name "CF2") (class "Default")
      (node (ref "U4") (pin "163") (pinfunction "P0_6/AN102_163") (pintype "bidirectional"))
      (node (ref "U6") (pin "26") (pinfunction "CF2_26") (pintype "output"))
    )
    (net (code "6") (name "CF3") (class "Default")
      (node (ref "U4") (pin "161") (pinfunction "P0_8/AN003_161") (pintype "bidirectional"))
      (node (ref "U6") (pin "27") (pinfunction "CF3_27") (pintype "output"))
    )
    (net (code "7") (name "CF4") (class "Default")
      (node (ref "U4") (pin "160") (pinfunction "P0_9/AN004_160") (pintype "bidirectional"))
      (node (ref "U6") (pin "28") (pinfunction "CF4_28") (pintype "output"))
    )
    (net (code "8") (name "CRS_DV") (class "Default")
      (node (ref "R33") (pin "P$2") (pinfunction "2_P$2") (pintype "passive"))
      (node (ref "U3") (pin "15") (pinfunction "CRS_DV/PHYAD[1:0]_15") (pintype "bidirectional"))
    )
    (net (code "9") (name "DMA") (class "Default")
      (node (ref "U4") (pin "122") (pinfunction "P6_0_122") (pintype "bidirectional"))
      (node (ref "U6") (pin "36") (pinfunction "DMA_CTRL_36") (pintype "input"))
    )
    (net (code "10") (name "ETH") (class "Default")
      (node (ref "U3") (pin "16") (pinfunction "REF_CLK_16") (pintype "bidirectional"))
      (node (ref "U4") (pin "9") (pinfunction "P7_1_9") (pintype "bidirectional"))
    )
    (net (code "11") (name "ETH_CRS_DV") (class "Default")
      (node (ref "R33") (pin "P$1") (pinfunction "1_P$1") (pintype "passive"))
      (node (ref "U4") (pin "13") (pinfunction "P7_5_13") (pintype "bidirectional"))
    )
    (net (code "12") (name "ETH_IRQ14") (class "Default")
      (node (ref "R26") (pin "P$1") (pinfunction "1_P$1") (pintype "passive"))
      (node (ref "U3") (pin "18") (pinfunction "INTRP_18") (pintype "bidirectional"))
      (node (ref "U4") (pin "159") (pinfunction "P0_10/AN103_159") (pintype "bidirectional"))
    )
    (net (code "13") (name "ETH_MDC") (class "Default")
      (node (ref "R28") (pin "P$1") (pinfunction "1_P$1") (pintype "passive"))
      (node (ref "U3") (pin "11") (pinfunction "MDC_11") (pintype "input"))
      (node (ref "U4") (pin "4") (pinfunction "P4_3_4") (pintype "bidirectional"))
    )
    (net (code "14") (name "ETH_MDIO") (class "Default")
      (node (ref "R29") (pin "P$1") (pinfunction "1_P$1") (pintype "passive"))
      (node (ref "U3") (pin "10") (pinfunction "MDIO_10") (pintype "bidirectional"))
      (node (ref "U4") (pin "5") (pinfunction "P4_4_5") (pintype "bidirectional"))
    )
    (net (code "15") (name "ETH_RESET") (class "Default")
      (node (ref "R27") (pin "P$1") (pinfunction "1_P$1") (pintype "passive"))
      (node (ref "U$4") (pin "P$1") (pinfunction "1_P$1") (pintype "passive"))
      (node (ref "U3") (pin "24") (pinfunction "~{RST}_24") (pintype "input"))
      (node (ref "U4") (pin "172") (pinfunction "P8_6_172") (pintype "bidirectional"))
    )
    (net (code "16") (name "ETH_RXD0") (class "Default")
      (node (ref "R31") (pin "P$1") (pinfunction "1_P$1") (pintype "passive"))
      (node (ref "U4") (pin "10") (pinfunction "P7_2_10") (pintype "bidirectional"))
    )
    (net (code "17") (name "ETH_RXD1") (class "Default")
      (node (ref "R30") (pin "P$1") (pinfunction "1_P$1") (pintype "passive"))
      (node (ref "U4") (pin "11") (pinfunction "P7_3_11") (pintype "bidirectional"))
    )
    (net (code "18") (name "ETH_RX_ER") (class "Default")
      (node (ref "R32") (pin "P$1") (pinfunction "1_P$1") (pintype "passive"))
      (node (ref "U4") (pin "12") (pinfunction "P7_4_12") (pintype "bidirectional"))
    )
    (net (code "19") (name "ETH_TXD0") (class "Default")
      (node (ref "U3") (pin "20") (pinfunction "TXD0_20") (pintype "input"))
      (node (ref "U4") (pin "8") (pinfunction "P7_0_8") (pintype "bidirectional"))
    )
    (net (code "20") (name "ETH_TXD1") (class "Default")
      (node (ref "U3") (pin "21") (pinfunction "TXD1_21") (pintype "bidirectional"))
      (node (ref "U4") (pin "7") (pinfunction "P4_6_7") (pintype "bidirectional"))
    )
    (net (code "21") (name "ETH_TXD_EN") (class "Default")
      (node (ref "U3") (pin "19") (pinfunction "TXEN_19") (pintype "input"))
      (node (ref "U4") (pin "6") (pinfunction "P4_5_6") (pintype "bidirectional"))
    )
    (net (code "22") (name "GND") (class "Default")
      (node (ref "C1") (pin "P$1") (pinfunction "1_P$1") (pintype "passive"))
      (node (ref "C10") (pin "P$1") (pinfunction "1_P$1") (pintype "passive"))
      (node (ref "C100") (pin "P$2") (pinfunction "2_P$2") (pintype "passive"))
      (node (ref "C101") (pin "2") (pinfunction "2_2") (pintype "passive"))
      (node (ref "C11") (pin "P$2") (pinfunction "2_P$2") (pintype "passive"))
      (node (ref "C13") (pin "P$1") (pinfunction "1_P$1") (pintype "passive"))
      (node (ref "C14") (pin "P$1") (pinfunction "1_P$1") (pintype "passive"))
      (node (ref "C15") (pin "2") (pinfunction "2_2") (pintype "passive"))
      (node (ref "C16") (pin "P$2") (pinfunction "2_P$2") (pintype "passive"))
      (node (ref "C2") (pin "P$1") (pinfunction "1_P$1") (pintype "passive"))
      (node (ref "C30") (pin "P$1") (pinfunction "1_P$1") (pintype "passive"))
      (node (ref "C31") (pin "P$2") (pinfunction "2_P$2") (pintype "passive"))
      (node (ref "C32") (pin "P$2") (pinfunction "2_P$2") (pintype "passive"))
      (node (ref "C36") (pin "P$1") (pinfunction "1_P$1") (pintype "passive"))
      (node (ref "C37") (pin "P$1") (pinfunction "1_P$1") (pintype "passive"))
      (node (ref "C38") (pin "P$2") (pinfunction "2_P$2") (pintype "passive"))
      (node (ref "C39") (pin "P$2") (pinfunction "2_P$2") (pintype "passive"))
      (node (ref "C40") (pin "P$2") (pinfunction "2_P$2") (pintype "passive"))
      (node (ref "C41") (pin "P$2") (pinfunction "2_P$2") (pintype "passive"))
      (node (ref "C42") (pin "P$2") (pinfunction "2_P$2") (pintype "passive"))
      (node (ref "C43") (pin "2") (pinfunction "2_2") (pintype "passive"))
      (node (ref "C44") (pin "P$2") (pinfunction "2_P$2") (pintype "passive"))
      (node (ref "C45") (pin "P$2") (pinfunction "2_P$2") (pintype "passive"))
      (node (ref "C46") (pin "P$2") (pinfunction "2_P$2") (pintype "passive"))
      (node (ref "C47") (pin "P$2") (pinfunction "2_P$2") (pintype "passive"))
      (node (ref "C48") (pin "2") (pinfunction "2_2") (pintype "passive"))
      (node (ref "C49") (pin "P$2") (pinfunction "2_P$2") (pintype "passive"))
      (node (ref "C5") (pin "P$2") (pinfunction "2_P$2") (pintype "passive"))
      (node (ref "C50") (pin "P$2") (pinfunction "2_P$2") (pintype "passive"))
      (node (ref "C51") (pin "P$2") (pinfunction "2_P$2") (pintype "passive"))
      (node (ref "C52") (pin "P$2") (pinfunction "2_P$2") (pintype "passive"))
      (node (ref "C53") (pin "P$2") (pinfunction "2_P$2") (pintype "passive"))
      (node (ref "C54") (pin "P$1") (pinfunction "1_P$1") (pintype "passive"))
      (node (ref "C55") (pin "P$1") (pinfunction "1_P$1") (pintype "passive"))
      (node (ref "C56") (pin "P$1") (pinfunction "1_P$1") (pintype "passive"))
      (node (ref "C57") (pin "P$2") (pinfunction "2_P$2") (pintype "passive"))
      (node (ref "C58") (pin "P$2") (pinfunction "2_P$2") (pintype "passive"))
      (node (ref "C59") (pin "P$2") (pinfunction "2_P$2") (pintype "passive"))
      (node (ref "C60") (pin "P$2") (pinfunction "2_P$2") (pintype "passive"))
      (node (ref "C61") (pin "P$1") (pinfunction "1_P$1") (pintype "passive"))
      (node (ref "C71") (pin "P$2") (pinfunction "2_P$2") (pintype "passive"))
      (node (ref "C72") (pin "P$1") (pinfunction "1_P$1") (pintype "passive"))
      (node (ref "C73") (pin "P$2") (pinfunction "2_P$2") (pintype "passive"))
      (node (ref "C74") (pin "P$1") (pinfunction "1_P$1") (pintype "passive"))
      (node (ref "C75") (pin "P$2") (pinfunction "2_P$2") (pintype "passive"))
      (node (ref "C76") (pin "P$1") (pinfunction "1_P$1") (pintype "passive"))
      (node (ref "C77") (pin "P$2") (pinfunction "2_P$2") (pintype "passive"))
      (node (ref "C78") (pin "P$1") (pinfunction "1_P$1") (pintype "passive"))
      (node (ref "C79") (pin "P$1") (pinfunction "1_P$1") (pintype "passive"))
      (node (ref "C8") (pin "P$2") (pinfunction "2_P$2") (pintype "passive"))
      (node (ref "C80") (pin "P$1") (pinfunction "1_P$1") (pintype "passive"))
      (node (ref "C81") (pin "P$1") (pinfunction "1_P$1") (pintype "passive"))
      (node (ref "C82") (pin "P$1") (pinfunction "1_P$1") (pintype "passive"))
      (node (ref "C83") (pin "P$1") (pinfunction "1_P$1") (pintype "passive"))
      (node (ref "C84") (pin "P$1") (pinfunction "1_P$1") (pintype "passive"))
      (node (ref "C85") (pin "P$2") (pinfunction "2_P$2") (pintype "passive"))
      (node (ref "C86") (pin "P$2") (pinfunction "2_P$2") (pintype "passive"))
      (node (ref "C87") (pin "P$1") (pinfunction "1_P$1") (pintype "passive"))
      (node (ref "C88") (pin "P$1") (pinfunction "1_P$1") (pintype "passive"))
      (node (ref "C89") (pin "P$2") (pinfunction "2_P$2") (pintype "passive"))
      (node (ref "C90") (pin "P$2") (pinfunction "2_P$2") (pintype "passive"))
      (node (ref "C91") (pin "P$2") (pinfunction "2_P$2") (pintype "passive"))
      (node (ref "C92") (pin "P$2") (pinfunction "2_P$2") (pintype "passive"))
      (node (ref "C93") (pin "P$2") (pinfunction "P$2_P$2") (pintype "bidirectional"))
      (node (ref "C94") (pin "P$2") (pinfunction "2_P$2") (pintype "passive"))
      (node (ref "C95") (pin "P$2") (pinfunction "2_P$2") (pintype "passive"))
      (node (ref "C96") (pin "2") (pinfunction "2_2") (pintype "passive"))
      (node (ref "C97") (pin "P$2") (pinfunction "2_P$2") (pintype "passive"))
      (node (ref "C98") (pin "P$2") (pinfunction "2_P$2") (pintype "passive"))
      (node (ref "C99") (pin "2") (pinfunction "2_2") (pintype "passive"))
      (node (ref "IC3") (pin "2") (pinfunction "GND_2") (pintype "power_in"))
      (node (ref "IC4") (pin "2") (pinfunction "GND_2") (pintype "power_in"))
      (node (ref "J10") (pin "P$2") (pinfunction "P$2_P$2") (pintype "bidirectional"))
      (node (ref "J11") (pin "10") (pinfunction "10_10") (pintype "passive"))
      (node (ref "J11") (pin "6") (pinfunction "6_6") (pintype "passive"))
      (node (ref "J11") (pin "8") (pinfunction "8_8") (pintype "passive"))
      (node (ref "J2") (pin "P$5") (pinfunction "GND_P$5") (pintype "bidirectional"))
      (node (ref "J3") (pin "GND") (pinfunction "GND_GND") (pintype "power_in"))
      (node (ref "J4") (pin "10") (pinfunction "GLO_10") (pintype "bidirectional"))
      (node (ref "J4") (pin "8") (pinfunction "P8_8") (pintype "bidirectional"))
      (node (ref "LED3") (pin "C") (pinfunction "C_C") (pintype "passive"))
      (node (ref "LED4") (pin "C") (pinfunction "C_C") (pintype "passive"))
      (node (ref "R107") (pin "P$2") (pinfunction "2_P$2") (pintype "passive"))
      (node (ref "R108") (pin "P$2") (pinfunction "2_P$2") (pintype "passive"))
      (node (ref "R116") (pin "P$2") (pinfunction "2_P$2") (pintype "passive"))
      (node (ref "R117") (pin "P$2") (pinfunction "2_P$2") (pintype "passive"))
      (node (ref "R125") (pin "P$2") (pinfunction "2_P$2") (pintype "passive"))
      (node (ref "R126") (pin "P$2") (pinfunction "2_P$2") (pintype "passive"))
      (node (ref "R16") (pin "P$1") (pinfunction "1_P$1") (pintype "passive"))
      (node (ref "R17") (pin "P$1") (pinfunction "1_P$1") (pintype "passive"))
      (node (ref "R19") (pin "P$1") (pinfunction "1_P$1") (pintype "passive"))
      (node (ref "R25") (pin "P$1") (pinfunction "1_P$1") (pintype "passive"))
      (node (ref "R7") (pin "P$1") (pinfunction "1_P$1") (pintype "passive"))
      (node (ref "R77") (pin "P$1") (pinfunction "1_P$1") (pintype "passive"))
      (node (ref "R80") (pin "P$1") (pinfunction "1_P$1") (pintype "passive"))
      (node (ref "R83") (pin "P$1") (pinfunction "1_P$1") (pintype "passive"))
      (node (ref "R86") (pin "P$1") (pinfunction "1_P$1") (pintype "passive"))
      (node (ref "R89") (pin "P$1") (pinfunction "1_P$1") (pintype "passive"))
      (node (ref "R92") (pin "P$1") (pinfunction "1_P$1") (pintype "passive"))
      (node (ref "R95") (pin "P$1") (pinfunction "1_P$1") (pintype "passive"))
      (node (ref "R98") (pin "P$1") (pinfunction "1_P$1") (pintype "passive"))
      (node (ref "U$1") (pin "P$3") (pinfunction "P$3_P$3") (pintype "bidirectional"))
      (node (ref "U$3") (pin "2") (pinfunction "2_2") (pintype "bidirectional"))
      (node (ref "U$3") (pin "4") (pinfunction "4_4") (pintype "bidirectional"))
      (node (ref "U$4") (pin "P$2") (pinfunction "2_P$2") (pintype "passive"))
      (node (ref "U$6") (pin "2") (pinfunction "2_2") (pintype "bidirectional"))
      (node (ref "U$6") (pin "4") (pinfunction "4_4") (pintype "bidirectional"))
      (node (ref "U$7") (pin "P$2") (pinfunction "P$2_P$2") (pintype "bidirectional"))
      (node (ref "U$8") (pin "N-") (pinfunction "-_N-") (pintype "passive"))
      (node (ref "U2") (pin "2") (pinfunction "GND_2") (pintype "input"))
      (node (ref "U3") (pin "22") (pinfunction "GND_22") (pintype "power_in"))
      (node (ref "U3") (pin "25") (pinfunction "25_25") (pintype "passive"))
      (node (ref "U4") (pin "111") (pinfunction "VSS(IO)5_111") (pintype "bidirectional"))
      (node (ref "U4") (pin "124") (pinfunction "VSS(IO)6_124") (pintype "bidirectional"))
      (node (ref "U4") (pin "139") (pinfunction "VSS(IO)7_139") (pintype "bidirectional"))
      (node (ref "U4") (pin "150") (pinfunction "VSS(IO)8_150") (pintype "bidirectional"))
      (node (ref "U4") (pin "153") (pinfunction "VREFL_153") (pintype "bidirectional"))
      (node (ref "U4") (pin "156") (pinfunction "AVSS0_156") (pintype "bidirectional"))
      (node (ref "U4") (pin "157") (pinfunction "VREFL0_157") (pintype "bidirectional"))
      (node (ref "U4") (pin "170") (pinfunction "VSS(IO)9_170") (pintype "bidirectional"))
      (node (ref "U4") (pin "22") (pinfunction "VSS1_22") (pintype "bidirectional"))
      (node (ref "U4") (pin "28") (pinfunction "AVSS_USBHS_28") (pintype "bidirectional"))
      (node (ref "U4") (pin "29") (pinfunction "PVSS_USBHS_29") (pintype "bidirectional"))
      (node (ref "U4") (pin "30") (pinfunction "VSS2_USBHS_30") (pintype "bidirectional"))
      (node (ref "U4") (pin "33") (pinfunction "VSS1_USBHS_33") (pintype "bidirectional"))
      (node (ref "U4") (pin "35") (pinfunction "VSSIO_35") (pintype "bidirectional"))
      (node (ref "U4") (pin "45") (pinfunction "VSS_USB_45") (pintype "bidirectional"))
      (node (ref "U4") (pin "60") (pinfunction "VSS(IO)2_60") (pintype "bidirectional"))
      (node (ref "U4") (pin "63") (pinfunction "VSS(IO/DCDC)_63") (pintype "bidirectional"))
      (node (ref "U4") (pin "66") (pinfunction "VCC_DCDC(IO/DCDC)_66") (pintype "bidirectional"))
      (node (ref "U4") (pin "83") (pinfunction "VSS(IO)3_83") (pintype "bidirectional"))
      (node (ref "U4") (pin "98") (pinfunction "VSS(IO)4_98") (pintype "bidirectional"))
      (node (ref "U6") (pin "12") (pinfunction "AGND_12") (pintype "power_in"))
      (node (ref "U6") (pin "19") (pinfunction "DGND_2_19") (pintype "power_in"))
      (node (ref "U6") (pin "2") (pinfunction "AGND_2_2") (pintype "power_in"))
      (node (ref "U6") (pin "32") (pinfunction "TEST_32") (pintype "input"))
      (node (ref "U6") (pin "44") (pinfunction "DGND_3_44") (pintype "power_in"))
      (node (ref "U6") (pin "47") (pinfunction "DGND_47") (pintype "power_in"))
      (node (ref "U7") (pin "P$3") (pinfunction "VOUT-_P$3") (pintype "bidirectional"))
      (node (ref "U7") (pin "P$6") (pinfunction "AC_N_P$6") (pintype "bidirectional"))
      (node (ref "X4") (pin "2") (pinfunction "2_2") (pintype "bidirectional"))
      (node (ref "X4") (pin "4") (pinfunction "4_4") (pintype "bidirectional"))
    )
    (net (code "23") (name "GNDE") (class "Default")
      (node (ref "J2") (pin "P$6") (pinfunction "SHIELD1_P$6") (pintype "bidirectional"))
      (node (ref "J2") (pin "P$7") (pinfunction "SHIELD2_P$7") (pintype "bidirectional"))
      (node (ref "J2") (pin "P$8") (pinfunction "SHIELD3_P$8") (pintype "bidirectional"))
      (node (ref "J2") (pin "P$9") (pinfunction "SHIELD4_P$9") (pintype "bidirectional"))
      (node (ref "J3") (pin "SHLD1") (pinfunction "SHIELD_1_SHLD1") (pintype "bidirectional"))
      (node (ref "J3") (pin "SHLD2") (pinfunction "SHIELD_2_SHLD2") (pintype "bidirectional"))
      (node (ref "J4") (pin "13") (pinfunction "GNDE0_13") (pintype "bidirectional"))
      (node (ref "J4") (pin "14") (pinfunction "GNDE1_14") (pintype "bidirectional"))
    )
    (net (code "24") (name "GP4") (class "Default")
      (node (ref "U4") (pin "49") (pinfunction "P2_7_49") (pintype "bidirectional"))
    )
    (net (code "25") (name "IAN") (class "Default")
      (node (ref "C72") (pin "P$2") (pinfunction "2_P$2") (pintype "passive"))
      (node (ref "R81") (pin "P$2") (pinfunction "2_P$2") (pintype "passive"))
      (node (ref "U6") (pin "4") (pinfunction "I1N_4") (pintype "input"))
    )
    (net (code "26") (name "IAP") (class "Default")
      (node (ref "C71") (pin "P$1") (pinfunction "1_P$1") (pintype "passive"))
      (node (ref "R78") (pin "P$1") (pinfunction "1_P$1") (pintype "passive"))
      (node (ref "U6") (pin "3") (pinfunction "I1P_3") (pintype "input"))
    )
    (net (code "27") (name "IA_1+") (class "Default")
      (node (ref "J5") (pin "P$1") (pinfunction "P$1_P$1") (pintype "bidirectional"))
      (node (ref "R76") (pin "P$1") (pinfunction "1_P$1") (pintype "passive"))
    )
    (net (code "28") (name "IA_2-") (class "Default")
      (node (ref "J5") (pin "P$2") (pinfunction "P$2_P$2") (pintype "bidirectional"))
      (node (ref "R79") (pin "P$2") (pinfunction "2_P$2") (pintype "passive"))
    )
    (net (code "29") (name "IBN") (class "Default")
      (node (ref "C74") (pin "P$2") (pinfunction "2_P$2") (pintype "passive"))
      (node (ref "R87") (pin "P$2") (pinfunction "2_P$2") (pintype "passive"))
      (node (ref "U6") (pin "6") (pinfunction "I2N_6") (pintype "input"))
    )
    (net (code "30") (name "IBP") (class "Default")
      (node (ref "C73") (pin "P$1") (pinfunction "1_P$1") (pintype "passive"))
      (node (ref "R84") (pin "P$1") (pinfunction "1_P$1") (pintype "passive"))
      (node (ref "U6") (pin "5") (pinfunction "I2P_5") (pintype "input"))
    )
    (net (code "31") (name "IB_1+") (class "Default")
      (node (ref "J5") (pin "P$3") (pinfunction "P$3_P$3") (pintype "bidirectional"))
      (node (ref "R82") (pin "P$1") (pinfunction "1_P$1") (pintype "passive"))
    )
    (net (code "32") (name "IB_2-") (class "Default")
      (node (ref "J5") (pin "P$4") (pinfunction "P$4_P$4") (pintype "bidirectional"))
      (node (ref "R85") (pin "P$2") (pinfunction "2_P$2") (pintype "passive"))
    )
    (net (code "33") (name "ICN") (class "Default")
      (node (ref "C76") (pin "P$2") (pinfunction "2_P$2") (pintype "passive"))
      (node (ref "R93") (pin "P$2") (pinfunction "2_P$2") (pintype "passive"))
      (node (ref "U6") (pin "8") (pinfunction "I3N_8") (pintype "input"))
    )
    (net (code "34") (name "ICP") (class "Default")
      (node (ref "C75") (pin "P$1") (pinfunction "1_P$1") (pintype "passive"))
      (node (ref "R90") (pin "P$1") (pinfunction "1_P$1") (pintype "passive"))
      (node (ref "U6") (pin "7") (pinfunction "I3P_7") (pintype "input"))
    )
    (net (code "35") (name "IC_1+") (class "Default")
      (node (ref "J1") (pin "P$1") (pinfunction "P$1_P$1") (pintype "bidirectional"))
      (node (ref "R88") (pin "P$1") (pinfunction "1_P$1") (pintype "passive"))
    )
    (net (code "36") (name "IC_2-") (class "Default")
      (node (ref "J1") (pin "P$2") (pinfunction "P$2_P$2") (pintype "bidirectional"))
      (node (ref "R91") (pin "P$2") (pinfunction "2_P$2") (pintype "passive"))
    )
    (net (code "37") (name "ID") (class "Default")
      (node (ref "J2") (pin "P$4") (pinfunction "ID_P$4") (pintype "bidirectional"))
    )
    (net (code "38") (name "IIC_0_SCL") (class "Default")
      (node (ref "U4") (pin "1") (pinfunction "P4_0_1") (pintype "bidirectional"))
    )
    (net (code "39") (name "IIC_0_SDA") (class "Default")
      (node (ref "U4") (pin "2") (pinfunction "P4_1_2") (pintype "bidirectional"))
    )
    (net (code "40") (name "INN") (class "Default")
      (node (ref "C78") (pin "P$2") (pinfunction "2_P$2") (pintype "passive"))
      (node (ref "R99") (pin "P$2") (pinfunction "2_P$2") (pintype "passive"))
      (node (ref "U6") (pin "10") (pinfunction "I4N_10") (pintype "input"))
    )
    (net (code "41") (name "INP") (class "Default")
      (node (ref "C77") (pin "P$1") (pinfunction "1_P$1") (pintype "passive"))
      (node (ref "R96") (pin "P$1") (pinfunction "1_P$1") (pintype "passive"))
      (node (ref "U6") (pin "9") (pinfunction "I4P_9") (pintype "input"))
    )
    (net (code "42") (name "INT_AI_LS_0") (class "Default")
      (node (ref "U4") (pin "3") (pinfunction "P4_2_3") (pintype "bidirectional"))
    )
    (net (code "43") (name "INT_AI_LS_1") (class "Default")
      (node (ref "U4") (pin "43") (pinfunction "P4_8_43") (pintype "bidirectional"))
    )
    (net (code "44") (name "IN_1+") (class "Default")
      (node (ref "J1") (pin "P$3") (pinfunction "P$3_P$3") (pintype "bidirectional"))
      (node (ref "R94") (pin "P$1") (pinfunction "1_P$1") (pintype "passive"))
    )
    (net (code "45") (name "IN_2-") (class "Default")
      (node (ref "J1") (pin "P$4") (pinfunction "P$4_P$4") (pintype "bidirectional"))
      (node (ref "R97") (pin "P$2") (pinfunction "2_P$2") (pintype "passive"))
    )
    (net (code "46") (name "IRQ0") (class "Default")
      (node (ref "U4") (pin "86") (pinfunction "P3_2_86") (pintype "bidirectional"))
      (node (ref "U6") (pin "30") (pinfunction "IRQ0_30") (pintype "output"))
    )
    (net (code "47") (name "IRQ1") (class "Default")
      (node (ref "U4") (pin "87") (pinfunction "P3_1_87") (pintype "bidirectional"))
      (node (ref "U6") (pin "31") (pinfunction "IRQ1_31") (pintype "output"))
    )
    (net (code "48") (name "LED1{slash}SPEED") (class "Default")
      (node (ref "J4") (pin "11") (pinfunction "YLO_11") (pintype "bidirectional"))
      (node (ref "U3") (pin "23") (pinfunction "LED0/ANEN_SPEED_23") (pintype "bidirectional"))
    )
    (net (code "49") (name "M0_DIR") (class "Default")
      (node (ref "U4") (pin "39") (pinfunction "P4_12_39") (pintype "bidirectional"))
    )
    (net (code "50") (name "M0_STEP") (class "Default")
      (node (ref "U4") (pin "16") (pinfunction "PB_0_16") (pintype "bidirectional"))
    )
    (net (code "51") (name "M1_DIR") (class "Default")
      (node (ref "U4") (pin "40") (pinfunction "P4_11_40") (pintype "bidirectional"))
    )
    (net (code "52") (name "M1_STEP") (class "Default")
      (node (ref "U4") (pin "36") (pinfunction "P4_15_36") (pintype "bidirectional"))
    )
    (net (code "53") (name "M2_DIR") (class "Default")
      (node (ref "U4") (pin "41") (pinfunction "P4_10_41") (pintype "bidirectional"))
    )
    (net (code "54") (name "M2_STEP") (class "Default")
      (node (ref "U4") (pin "37") (pinfunction "P4_14_37") (pintype "bidirectional"))
    )
    (net (code "55") (name "M3_DIR") (class "Default")
      (node (ref "U4") (pin "42") (pinfunction "P4_9_42") (pintype "bidirectional"))
    )
    (net (code "56") (name "M3_STEP") (class "Default")
      (node (ref "U4") (pin "38") (pinfunction "P4_13_38") (pintype "bidirectional"))
    )
    (net (code "57") (name "NC") (class "Default")
      (node (ref "J4") (pin "7") (pinfunction "P7_7") (pintype "bidirectional"))
    )
    (net (code "58") (name "Net-(C16-1)") (class "Default")
      (node (ref "C16") (pin "P$1") (pinfunction "1_P$1") (pintype "passive"))
      (node (ref "J2") (pin "P$1") (pinfunction "VBUS_P$1") (pintype "bidirectional"))
      (node (ref "R4") (pin "P$2") (pinfunction "2_P$2") (pintype "passive"))
      (node (ref "R7") (pin "P$2") (pinfunction "2_P$2") (pintype "passive"))
    )
    (net (code "59") (name "Net-(C31-1)") (class "Default")
      (node (ref "C31") (pin "P$1") (pinfunction "1_P$1") (pintype "passive"))
      (node (ref "U4") (pin "62") (pinfunction "VCL1_62") (pintype "bidirectional"))
    )
    (net (code "60") (name "Net-(C37-2)") (class "Default")
      (node (ref "C37") (pin "P$2") (pinfunction "2_P$2") (pintype "passive"))
      (node (ref "U4") (pin "148") (pinfunction "VCL2_148") (pintype "bidirectional"))
    )
    (net (code "61") (name "Net-(C38-1)") (class "Default")
      (node (ref "C38") (pin "P$1") (pinfunction "1_P$1") (pintype "passive"))
      (node (ref "U4") (pin "19") (pinfunction "VCLO_19") (pintype "bidirectional"))
    )
    (net (code "62") (name "Net-(C44-1)") (class "Default")
      (node (ref "C43") (pin "1") (pinfunction "1_1") (pintype "passive"))
      (node (ref "C44") (pin "P$1") (pinfunction "1_P$1") (pintype "passive"))
      (node (ref "FB2/2") (pin "2") (pinfunction "P$2_2") (pintype "bidirectional"))
      (node (ref "U3") (pin "2") (pinfunction "VDDA_3.3_2") (pintype "power_in"))
    )
    (net (code "63") (name "Net-(J2-D+)") (class "Default")
      (node (ref "J2") (pin "P$3") (pinfunction "D+_P$3") (pintype "bidirectional"))
      (node (ref "R6") (pin "P$2") (pinfunction "2_P$2") (pintype "passive"))
    )
    (net (code "64") (name "Net-(J2-D-)") (class "Default")
      (node (ref "J2") (pin "P$2") (pinfunction "D-_P$2") (pintype "bidirectional"))
      (node (ref "R5") (pin "P$2") (pinfunction "2_P$2") (pintype "passive"))
    )
    (net (code "65") (name "Net-(R16-2)") (class "Default")
      (node (ref "R16") (pin "P$2") (pinfunction "2_P$2") (pintype "passive"))
      (node (ref "U4") (pin "65") (pinfunction "VLO2(DCDC)_65") (pintype "bidirectional"))
    )
    (net (code "66") (name "Net-(R17-2)") (class "Default")
      (node (ref "R17") (pin "P$2") (pinfunction "2_P$2") (pintype "passive"))
      (node (ref "U4") (pin "64") (pinfunction "VLO1(DCDC)_64") (pintype "bidirectional"))
    )
    (net (code "67") (name "Net-(R19-2)") (class "Default")
      (node (ref "R19") (pin "P$2") (pinfunction "2_P$2") (pintype "passive"))
      (node (ref "U4") (pin "27") (pinfunction "USBHS_RREF_27") (pintype "bidirectional"))
    )
    (net (code "68") (name "Net-(R76-2)") (class "Default")
      (node (ref "R76") (pin "P$2") (pinfunction "2_P$2") (pintype "passive"))
      (node (ref "R77") (pin "P$2") (pinfunction "2_P$2") (pintype "passive"))
      (node (ref "R78") (pin "P$2") (pinfunction "2_P$2") (pintype "passive"))
    )
    (net (code "69") (name "Net-(R79-1)") (class "Default")
      (node (ref "R79") (pin "P$1") (pinfunction "1_P$1") (pintype "passive"))
      (node (ref "R80") (pin "P$2") (pinfunction "2_P$2") (pintype "passive"))
      (node (ref "R81") (pin "P$1") (pinfunction "1_P$1") (pintype "passive"))
    )
    (net (code "70") (name "Net-(R82-2)") (class "Default")
      (node (ref "R82") (pin "P$2") (pinfunction "2_P$2") (pintype "passive"))
      (node (ref "R83") (pin "P$2") (pinfunction "2_P$2") (pintype "passive"))
      (node (ref "R84") (pin "P$2") (pinfunction "2_P$2") (pintype "passive"))
    )
    (net (code "71") (name "Net-(R85-1)") (class "Default")
      (node (ref "R85") (pin "P$1") (pinfunction "1_P$1") (pintype "passive"))
      (node (ref "R86") (pin "P$2") (pinfunction "2_P$2") (pintype "passive"))
      (node (ref "R87") (pin "P$1") (pinfunction "1_P$1") (pintype "passive"))
    )
    (net (code "72") (name "Net-(R88-2)") (class "Default")
      (node (ref "R88") (pin "P$2") (pinfunction "2_P$2") (pintype "passive"))
      (node (ref "R89") (pin "P$2") (pinfunction "2_P$2") (pintype "passive"))
      (node (ref "R90") (pin "P$2") (pinfunction "2_P$2") (pintype "passive"))
    )
    (net (code "73") (name "Net-(R91-1)") (class "Default")
      (node (ref "R91") (pin "P$1") (pinfunction "1_P$1") (pintype "passive"))
      (node (ref "R92") (pin "P$2") (pinfunction "2_P$2") (pintype "passive"))
      (node (ref "R93") (pin "P$1") (pinfunction "1_P$1") (pintype "passive"))
    )
    (net (code "74") (name "Net-(R94-2)") (class "Default")
      (node (ref "R94") (pin "P$2") (pinfunction "2_P$2") (pintype "passive"))
      (node (ref "R95") (pin "P$2") (pinfunction "2_P$2") (pintype "passive"))
      (node (ref "R96") (pin "P$2") (pinfunction "2_P$2") (pintype "passive"))
    )
    (net (code "75") (name "Net-(R97-1)") (class "Default")
      (node (ref "R97") (pin "P$1") (pinfunction "1_P$1") (pintype "passive"))
      (node (ref "R98") (pin "P$2") (pinfunction "2_P$2") (pintype "passive"))
      (node (ref "R99") (pin "P$1") (pinfunction "1_P$1") (pintype "passive"))
    )
    (net (code "76") (name "Net-(R100-1)") (class "Default")
      (node (ref "R100") (pin "P$1") (pinfunction "1_P$1") (pintype "passive"))
      (node (ref "R101") (pin "P$1") (pinfunction "1_P$1") (pintype "passive"))
    )
    (net (code "77") (name "Net-(R101-2)") (class "Default")
      (node (ref "R101") (pin "P$2") (pinfunction "2_P$2") (pintype "passive"))
      (node (ref "R102") (pin "P$2") (pinfunction "2_P$2") (pintype "passive"))
    )
    (net (code "78") (name "Net-(R102-1)") (class "Default")
      (node (ref "R102") (pin "P$1") (pinfunction "1_P$1") (pintype "passive"))
      (node (ref "R103") (pin "P$1") (pinfunction "1_P$1") (pintype "passive"))
    )
    (net (code "79") (name "Net-(R103-2)") (class "Default")
      (node (ref "R103") (pin "P$2") (pinfunction "2_P$2") (pintype "passive"))
      (node (ref "R104") (pin "P$2") (pinfunction "2_P$2") (pintype "passive"))
    )
    (net (code "80") (name "Net-(R104-1)") (class "Default")
      (node (ref "R104") (pin "P$1") (pinfunction "1_P$1") (pintype "passive"))
      (node (ref "R105") (pin "P$1") (pinfunction "1_P$1") (pintype "passive"))
    )
    (net (code "81") (name "Net-(R105-2)") (class "Default")
      (node (ref "R105") (pin "P$2") (pinfunction "2_P$2") (pintype "passive"))
      (node (ref "R106") (pin "P$2") (pinfunction "2_P$2") (pintype "passive"))
    )
    (net (code "82") (name "Net-(R109-1)") (class "Default")
      (node (ref "R109") (pin "P$1") (pinfunction "1_P$1") (pintype "passive"))
      (node (ref "R110") (pin "P$1") (pinfunction "1_P$1") (pintype "passive"))
    )
    (net (code "83") (name "Net-(R110-2)") (class "Default")
      (node (ref "R110") (pin "P$2") (pinfunction "2_P$2") (pintype "passive"))
      (node (ref "R111") (pin "P$2") (pinfunction "2_P$2") (pintype "passive"))
    )
    (net (code "84") (name "Net-(R111-1)") (class "Default")
      (node (ref "R111") (pin "P$1") (pinfunction "1_P$1") (pintype "passive"))
      (node (ref "R112") (pin "P$1") (pinfunction "1_P$1") (pintype "passive"))
    )
    (net (code "85") (name "Net-(R112-2)") (class "Default")
      (node (ref "R112") (pin "P$2") (pinfunction "2_P$2") (pintype "passive"))
      (node (ref "R113") (pin "P$2") (pinfunction "2_P$2") (pintype "passive"))
    )
    (net (code "86") (name "Net-(R113-1)") (class "Default")
      (node (ref "R113") (pin "P$1") (pinfunction "1_P$1") (pintype "passive"))
      (node (ref "R114") (pin "P$1") (pinfunction "1_P$1") (pintype "passive"))
    )
    (net (code "87") (name "Net-(R114-2)") (class "Default")
      (node (ref "R114") (pin "P$2") (pinfunction "2_P$2") (pintype "passive"))
      (node (ref "R115") (pin "P$2") (pinfunction "2_P$2") (pintype "passive"))
    )
    (net (code "88") (name "Net-(R118-1)") (class "Default")
      (node (ref "R118") (pin "P$1") (pinfunction "1_P$1") (pintype "passive"))
      (node (ref "R119") (pin "P$1") (pinfunction "1_P$1") (pintype "passive"))
    )
    (net (code "89") (name "Net-(R119-2)") (class "Default")
      (node (ref "R119") (pin "P$2") (pinfunction "2_P$2") (pintype "passive"))
      (node (ref "R120") (pin "P$2") (pinfunction "2_P$2") (pintype "passive"))
    )
    (net (code "90") (name "Net-(R120-1)") (class "Default")
      (node (ref "R120") (pin "P$1") (pinfunction "1_P$1") (pintype "passive"))
      (node (ref "R121") (pin "P$1") (pinfunction "1_P$1") (pintype "passive"))
    )
    (net (code "91") (name "Net-(R121-2)") (class "Default")
      (node (ref "R121") (pin "P$2") (pinfunction "2_P$2") (pintype "passive"))
      (node (ref "R122") (pin "P$2") (pinfunction "2_P$2") (pintype "passive"))
    )
    (net (code "92") (name "Net-(R122-1)") (class "Default")
      (node (ref "R122") (pin "P$1") (pinfunction "1_P$1") (pintype "passive"))
      (node (ref "R123") (pin "P$1") (pinfunction "1_P$1") (pintype "passive"))
    )
    (net (code "93") (name "Net-(R123-2)") (class "Default")
      (node (ref "R123") (pin "P$2") (pinfunction "2_P$2") (pintype "passive"))
      (node (ref "R124") (pin "P$2") (pinfunction "2_P$2") (pintype "passive"))
    )
    (net (code "94") (name "Net-(R128-2)") (class "Default")
      (node (ref "LED3") (pin "A") (pinfunction "A_A") (pintype "passive"))
      (node (ref "R128") (pin "P$2") (pinfunction "2_P$2") (pintype "passive"))
    )
    (net (code "95") (name "Net-(R129-2)") (class "Default")
      (node (ref "LED4") (pin "A") (pinfunction "A_A") (pintype "passive"))
      (node (ref "R129") (pin "P$2") (pinfunction "2_P$2") (pintype "passive"))
    )
    (net (code "96") (name "OSCI") (class "Default")
      (node (ref "U$6") (pin "1") (pinfunction "1_1") (pintype "bidirectional"))
      (node (ref "U6") (pin "20") (pinfunction "OSCI_20") (pintype "input"))
    )
    (net (code "97") (name "OSCO") (class "Default")
      (node (ref "U$6") (pin "3") (pinfunction "3_3") (pintype "bidirectional"))
      (node (ref "U6") (pin "21") (pinfunction "OSCO_21") (pintype "output"))
    )
    (net (code "98") (name "P0_00") (class "Default")
      (node (ref "U4") (pin "169") (pinfunction "P0_0/AN0\\00_169") (pintype "bidirectional"))
    )
    (net (code "99") (name "P0_01") (class "Default")
      (node (ref "U4") (pin "168") (pinfunction "P0_1/AN001_168") (pintype "bidirectional"))
    )
    (net (code "100") (name "P0_02") (class "Default")
      (node (ref "U4") (pin "167") (pinfunction "P0_2/AN002_167") (pintype "bidirectional"))
    )
    (net (code "101") (name "P0_03") (class "Default")
      (node (ref "U4") (pin "166") (pinfunction "P0_3/PGAVSS000_166") (pintype "bidirectional"))
    )
    (net (code "102") (name "P0_04") (class "Default")
      (node (ref "U4") (pin "165") (pinfunction "P0_4/AN100_165") (pintype "bidirectional"))
    )
    (net (code "103") (name "P0_07") (class "Default")
      (node (ref "U4") (pin "162") (pinfunction "P0_7/PGVSS100_162") (pintype "bidirectional"))
    )
    (net (code "104") (name "P0_14") (class "Default")
      (node (ref "U4") (pin "152") (pinfunction "P0_14/DA0/AN005/AN105_152") (pintype "bidirectional"))
    )
    (net (code "105") (name "P0_15") (class "Default")
      (node (ref "U4") (pin "151") (pinfunction "P0_15/DA1/AN006/AN106_151") (pintype "bidirectional"))
    )
    (net (code "106") (name "P1_05") (class "Default")
      (node (ref "U4") (pin "127") (pinfunction "P1_5_127") (pintype "bidirectional"))
    )
    (net (code "107") (name "P1_11") (class "Default")
      (node (ref "U4") (pin "92") (pinfunction "P1_11_92") (pintype "bidirectional"))
    )
    (net (code "108") (name "P1_12") (class "Default")
      (node (ref "U4") (pin "93") (pinfunction "P1_12_93") (pintype "bidirectional"))
    )
    (net (code "109") (name "P1_13") (class "Default")
      (node (ref "U4") (pin "94") (pinfunction "P1_13_94") (pintype "bidirectional"))
    )
    (net (code "110") (name "P1_14") (class "Default")
      (node (ref "U4") (pin "95") (pinfunction "P1_14_95") (pintype "bidirectional"))
    )
    (net (code "111") (name "P1_15") (class "Default")
      (node (ref "U4") (pin "96") (pinfunction "P1_15_96") (pintype "bidirectional"))
    )
    (net (code "112") (name "P2_00") (class "Default")
      (node (ref "U4") (pin "69") (pinfunction "P2_0(INPUT_ONLY)_69") (pintype "bidirectional"))
    )
    (net (code "113") (name "P2_01") (class "Default")
      (node (ref "U4") (pin "68") (pinfunction "P2_1/MD_68") (pintype "bidirectional"))
    )
    (net (code "114") (name "P3_03") (class "Default")
      (node (ref "U4") (pin "85") (pinfunction "P3_3_85") (pintype "bidirectional"))
    )
    (net (code "115") (name "P3_04") (class "Default")
      (node (ref "U4") (pin "82") (pinfunction "P3_4_82") (pintype "bidirectional"))
    )
    (net (code "116") (name "P3_05") (class "Default")
      (node (ref "U4") (pin "81") (pinfunction "P3_5_81") (pintype "bidirectional"))
    )
    (net (code "117") (name "P3_06") (class "Default")
      (node (ref "U4") (pin "80") (pinfunction "P3_6_80") (pintype "bidirectional"))
    )
    (net (code "118") (name "P3_07") (class "Default")
      (node (ref "U4") (pin "79") (pinfunction "P3_7_79") (pintype "bidirectional"))
    )
    (net (code "119") (name "P3_09") (class "Default")
      (node (ref "U4") (pin "77") (pinfunction "P3_9_77") (pintype "bidirectional"))
    )
    (net (code "120") (name "P3_10") (class "Default")
      (node (ref "U4") (pin "76") (pinfunction "P3_10_76") (pintype "bidirectional"))
    )
    (net (code "121") (name "P3_11") (class "Default")
      (node (ref "U4") (pin "75") (pinfunction "P3_11_75") (pintype "bidirectional"))
    )
    (net (code "122") (name "P3_12") (class "Default")
      (node (ref "U4") (pin "74") (pinfunction "P3_12_74") (pintype "bidirectional"))
    )
    (net (code "123") (name "P5_11") (class "Default")
      (node (ref "U4") (pin "176") (pinfunction "P5_11_176") (pintype "bidirectional"))
    )
    (net (code "124") (name "P5_12") (class "Default")
      (node (ref "U4") (pin "175") (pinfunction "P5_12_175") (pintype "bidirectional"))
    )
    (net (code "125") (name "P5_13") (class "Default")
      (node (ref "U4") (pin "174") (pinfunction "P5_13_174") (pintype "bidirectional"))
    )
    (net (code "126") (name "P6_02") (class "Default")
      (node (ref "U4") (pin "120") (pinfunction "P6_2_120") (pintype "bidirectional"))
    )
    (net (code "127") (name "P6_03") (class "Default")
      (node (ref "U4") (pin "119") (pinfunction "P6_3_119") (pintype "bidirectional"))
    )
    (net (code "128") (name "P6_04") (class "Default")
      (node (ref "U4") (pin "118") (pinfunction "P6_4_118") (pintype "bidirectional"))
    )
    (net (code "129") (name "P6_05") (class "Default")
      (node (ref "U4") (pin "117") (pinfunction "P6_5_117") (pintype "bidirectional"))
    )
    (net (code "130") (name "P6_06") (class "Default")
      (node (ref "U4") (pin "116") (pinfunction "P6_6_116") (pintype "bidirectional"))
    )
    (net (code "131") (name "P6_07") (class "Default")
      (node (ref "U4") (pin "115") (pinfunction "P6_7_115") (pintype "bidirectional"))
    )
    (net (code "132") (name "P6_08") (class "Default")
      (node (ref "U4") (pin "99") (pinfunction "P6_8_99") (pintype "bidirectional"))
    )
    (net (code "133") (name "P6_09") (class "Default")
      (node (ref "U4") (pin "100") (pinfunction "P6_9_100") (pintype "bidirectional"))
    )
    (net (code "134") (name "P6_10") (class "Default")
      (node (ref "U4") (pin "101") (pinfunction "P6_10_101") (pintype "bidirectional"))
    )
    (net (code "135") (name "P6_11") (class "Default")
      (node (ref "U4") (pin "102") (pinfunction "P6_11_102") (pintype "bidirectional"))
    )
    (net (code "136") (name "P6_12") (class "Default")
      (node (ref "U4") (pin "103") (pinfunction "P6_12_103") (pintype "bidirectional"))
    )
    (net (code "137") (name "P6_13") (class "Default")
      (node (ref "U4") (pin "104") (pinfunction "P6_13_104") (pintype "bidirectional"))
    )
    (net (code "138") (name "P6_14") (class "Default")
      (node (ref "U4") (pin "105") (pinfunction "P6_14_105") (pintype "bidirectional"))
    )
    (net (code "139") (name "P6_15") (class "Default")
      (node (ref "U4") (pin "106") (pinfunction "P6_15_106") (pintype "bidirectional"))
    )
    (net (code "140") (name "P7_06") (class "Default")
      (node (ref "U4") (pin "14") (pinfunction "P7_6_14") (pintype "bidirectional"))
    )
    (net (code "141") (name "P7_07") (class "Default")
      (node (ref "U4") (pin "15") (pinfunction "P7_7_15") (pintype "bidirectional"))
    )
    (net (code "142") (name "P8_03") (class "Default")
      (node (ref "U4") (pin "136") (pinfunction "P8_3_136") (pintype "bidirectional"))
    )
    (net (code "143") (name "P8_04") (class "Default")
      (node (ref "U4") (pin "137") (pinfunction "P8_4_137") (pintype "bidirectional"))
    )
    (net (code "144") (name "P8_05") (class "Default")
      (node (ref "U4") (pin "173") (pinfunction "P8_5_173") (pintype "bidirectional"))
    )
    (net (code "145") (name "P9_05") (class "Default")
      (node (ref "U4") (pin "73") (pinfunction "P9_5_73") (pintype "bidirectional"))
    )
    (net (code "146") (name "P9_06") (class "Default")
      (node (ref "U4") (pin "72") (pinfunction "P9_6_72") (pintype "bidirectional"))
    )
    (net (code "147") (name "P9_07") (class "Default")
      (node (ref "U4") (pin "71") (pinfunction "P9_7_71") (pintype "bidirectional"))
    )
    (net (code "148") (name "P9_08") (class "Default")
      (node (ref "U4") (pin "70") (pinfunction "P9_8_70") (pintype "bidirectional"))
    )
    (net (code "149") (name "PA_00") (class "Default")
      (node (ref "U4") (pin "114") (pinfunction "PA_0_114") (pintype "bidirectional"))
    )
    (net (code "150") (name "PA_01") (class "Default")
      (node (ref "U4") (pin "113") (pinfunction "PA_1_113") (pintype "bidirectional"))
    )
    (net (code "151") (name "PA_08") (class "Default")
      (node (ref "U4") (pin "107") (pinfunction "PA_8_107") (pintype "bidirectional"))
    )
    (net (code "152") (name "PA_09") (class "Default")
      (node (ref "U4") (pin "108") (pinfunction "PA_9_108") (pintype "bidirectional"))
    )
    (net (code "153") (name "PA_10") (class "Default")
      (node (ref "U4") (pin "109") (pinfunction "PA_10_109") (pintype "bidirectional"))
    )
    (net (code "154") (name "PM0") (class "Default")
      (node (ref "U4") (pin "126") (pinfunction "P1_6_126") (pintype "bidirectional"))
      (node (ref "U6") (pin "33") (pinfunction "PM0_33") (pintype "input"))
    )
    (net (code "155") (name "PM1") (class "Default")
      (node (ref "U4") (pin "125") (pinfunction "P1_7_125") (pintype "bidirectional"))
      (node (ref "U6") (pin "34") (pinfunction "PM1_34") (pintype "input"))
    )
    (net (code "156") (name "R51") (class "Default")
      (node (ref "J4") (pin "12") (pinfunction "YHI_12") (pintype "bidirectional"))
      (node (ref "R23") (pin "P$1") (pinfunction "1_P$1") (pintype "passive"))
    )
    (net (code "157") (name "R52") (class "Default")
      (node (ref "J4") (pin "9") (pinfunction "GHI_9") (pintype "bidirectional"))
      (node (ref "R24") (pin "P$1") (pinfunction "1_P$1") (pintype "passive"))
    )
    (net (code "158") (name "RELAY_0") (class "Default")
      (node (ref "U4") (pin "59") (pinfunction "P9_1_59") (pintype "bidirectional"))
    )
    (net (code "159") (name "RELAY_1") (class "Default")
      (node (ref "U4") (pin "58") (pinfunction "P9_0_58") (pintype "bidirectional"))
    )
    (net (code "160") (name "RELAY_2") (class "Default")
      (node (ref "U4") (pin "57") (pinfunction "P3_15_57") (pintype "bidirectional"))
    )
    (net (code "161") (name "RELAY_3") (class "Default")
      (node (ref "U4") (pin "56") (pinfunction "P3_14_56") (pintype "bidirectional"))
    )
    (net (code "162") (name "RELAY_6") (class "Default")
      (node (ref "U4") (pin "51") (pinfunction "P2_5_51") (pintype "bidirectional"))
    )
    (net (code "163") (name "RELAY_7") (class "Default")
      (node (ref "U4") (pin "50") (pinfunction "P2_6_50") (pintype "bidirectional"))
    )
    (net (code "164") (name "RESET") (class "Default")
      (node (ref "C57") (pin "P$1") (pinfunction "1_P$1") (pintype "passive"))
      (node (ref "J11") (pin "9") (pinfunction "9_9") (pintype "passive"))
      (node (ref "R18") (pin "P$1") (pinfunction "1_P$1") (pintype "passive"))
      (node (ref "U4") (pin "67") (pinfunction "RES#_67") (pintype "bidirectional"))
    )
    (net (code "165") (name "REXT") (class "Default")
      (node (ref "C47") (pin "P$1") (pinfunction "1_P$1") (pintype "passive"))
      (node (ref "R25") (pin "P$2") (pinfunction "2_P$2") (pintype "passive"))
      (node (ref "U3") (pin "9") (pinfunction "REXT_9") (pintype "input"))
    )
    (net (code "166") (name "RST") (class "Default")
      (node (ref "C91") (pin "P$1") (pinfunction "1_P$1") (pintype "passive"))
      (node (ref "R127") (pin "P$1") (pinfunction "1_P$1") (pintype "passive"))
      (node (ref "U4") (pin "121") (pinfunction "P6_1_121") (pintype "bidirectional"))
      (node (ref "U6") (pin "41") (pinfunction "~{RESET}_41") (pintype "input"))
    )
    (net (code "167") (name "RXD0") (class "Default")
      (node (ref "R31") (pin "P$2") (pinfunction "2_P$2") (pintype "passive"))
      (node (ref "U3") (pin "13") (pinfunction "RXD0_13") (pintype "bidirectional"))
    )
    (net (code "168") (name "RXD1") (class "Default")
      (node (ref "R30") (pin "P$2") (pinfunction "2_P$2") (pintype "passive"))
      (node (ref "U3") (pin "12") (pinfunction "RXD1_12") (pintype "bidirectional"))
    )
    (net (code "169") (name "RXER") (class "Default")
      (node (ref "R32") (pin "P$2") (pinfunction "2_P$2") (pintype "passive"))
      (node (ref "U3") (pin "17") (pinfunction "RXER_17") (pintype "bidirectional"))
    )
    (net (code "170") (name "RXM") (class "Default")
      (node (ref "J4") (pin "6") (pinfunction "RD-_6") (pintype "bidirectional"))
      (node (ref "U3") (pin "3") (pinfunction "RXM_3") (pintype "bidirectional"))
    )
    (net (code "171") (name "RXP") (class "Default")
      (node (ref "J4") (pin "3") (pinfunction "RD+_3") (pintype "bidirectional"))
      (node (ref "U3") (pin "4") (pinfunction "RXP_4") (pintype "bidirectional"))
    )
    (net (code "172") (name "SD1_CD") (class "Default")
      (node (ref "U4") (pin "146") (pinfunction "P5_6/AN019_146") (pintype "bidirectional"))
    )
    (net (code "173") (name "SD1_CLK") (class "Default")
      (node (ref "U4") (pin "140") (pinfunction "P5_0/AN016_140") (pintype "bidirectional"))
    )
    (net (code "174") (name "SD1_CMD") (class "Default")
      (node (ref "U4") (pin "141") (pinfunction "P5_1/AN116_141") (pintype "bidirectional"))
    )
    (net (code "175") (name "SD1_DAT0") (class "Default")
      (node (ref "U4") (pin "142") (pinfunction "P5_2/AN017_142") (pintype "bidirectional"))
    )
    (net (code "176") (name "SD1_DAT1") (class "Default")
      (node (ref "U4") (pin "143") (pinfunction "P5_3/AN117_143") (pintype "bidirectional"))
    )
    (net (code "177") (name "SD1_DAT2") (class "Default")
      (node (ref "U4") (pin "144") (pinfunction "P5_4/AN018_144") (pintype "bidirectional"))
    )
    (net (code "178") (name "SD1_DAT3") (class "Default")
      (node (ref "U4") (pin "145") (pinfunction "P5_5/AN118_145") (pintype "bidirectional"))
    )
    (net (code "179") (name "SD1_WP") (class "Default")
      (node (ref "U4") (pin "147") (pinfunction "P5_7/AN119_147") (pintype "bidirectional"))
    )
    (net (code "180") (name "SPI_0_CS_0") (class "Default")
      (node (ref "U4") (pin "129") (pinfunction "P1_3_129") (pintype "bidirectional"))
      (node (ref "U6") (pin "37") (pinfunction "~{CS}_37") (pintype "bidirectional"))
    )
    (net (code "181") (name "SPI_0_MISO") (class "Default")
      (node (ref "U4") (pin "132") (pinfunction "P1_0_132") (pintype "bidirectional"))
      (node (ref "U6") (pin "39") (pinfunction "SDO_39") (pintype "bidirectional"))
    )
    (net (code "182") (name "SPI_0_MOSI") (class "Default")
      (node (ref "U4") (pin "131") (pinfunction "P1_1_131") (pintype "bidirectional"))
      (node (ref "U6") (pin "40") (pinfunction "SDI_40") (pintype "bidirectional"))
    )
    (net (code "183") (name "SPI_0_SCLK") (class "Default")
      (node (ref "U4") (pin "130") (pinfunction "P1_2_130") (pintype "bidirectional"))
      (node (ref "U6") (pin "38") (pinfunction "SCLK_38") (pintype "bidirectional"))
    )
    (net (code "184") (name "SPI_1_CS_0") (class "Default")
      (node (ref "U$1") (pin "P$7") (pinfunction "P$7_P$7") (pintype "bidirectional"))
      (node (ref "U4") (pin "55") (pinfunction "P3_13_55") (pintype "bidirectional"))
    )
    (net (code "185") (name "SPI_1_MISO") (class "Default")
      (node (ref "U$1") (pin "P$5") (pinfunction "P$5_P$5") (pintype "bidirectional"))
      (node (ref "U4") (pin "54") (pinfunction "P2_2_54") (pintype "bidirectional"))
    )
    (net (code "186") (name "SPI_1_MOSI") (class "Default")
      (node (ref "U$1") (pin "P$6") (pinfunction "P$6_P$6") (pintype "bidirectional"))
      (node (ref "U4") (pin "53") (pinfunction "P2_3_53") (pintype "bidirectional"))
    )
    (net (code "187") (name "SPI_1_SCLK") (class "Default")
      (node (ref "U$1") (pin "P$4") (pinfunction "P$4_P$4") (pintype "bidirectional"))
      (node (ref "U4") (pin "52") (pinfunction "P2_4_52") (pintype "bidirectional"))
    )
    (net (code "188") (name "TCK") (class "Default")
      (node (ref "J11") (pin "7") (pinfunction "7_7") (pintype "passive"))
      (node (ref "U4") (pin "88") (pinfunction "P3_0_88") (pintype "bidirectional"))
    )
    (net (code "189") (name "TDI") (class "Default")
      (node (ref "J11") (pin "1") (pinfunction "1_1") (pintype "passive"))
      (node (ref "U4") (pin "91") (pinfunction "P1_10_91") (pintype "bidirectional"))
    )
    (net (code "190") (name "TDO") (class "Default")
      (node (ref "J11") (pin "3") (pinfunction "3_3") (pintype "passive"))
      (node (ref "U4") (pin "90") (pinfunction "P1_9_90") (pintype "bidirectional"))
    )
    (net (code "191") (name "TMS") (class "Default")
      (node (ref "J11") (pin "5") (pinfunction "5_5") (pintype "passive"))
      (node (ref "U4") (pin "89") (pinfunction "P1_8_89") (pintype "bidirectional"))
    )
    (net (code "192") (name "TXM") (class "Default")
      (node (ref "J4") (pin "2") (pinfunction "TD-_2") (pintype "bidirectional"))
      (node (ref "U3") (pin "5") (pinfunction "TXM_5") (pintype "bidirectional"))
    )
    (net (code "193") (name "TXP") (class "Default")
      (node (ref "J4") (pin "1") (pinfunction "TD+_1") (pintype "bidirectional"))
      (node (ref "U3") (pin "6") (pinfunction "TXP_6") (pintype "bidirectional"))
    )
    (net (code "194") (name "UA") (class "Default")
      (node (ref "J9") (pin "P$1") (pinfunction "P$1_P$1") (pintype "bidirectional"))
      (node (ref "R100") (pin "P$2") (pinfunction "2_P$2") (pintype "passive"))
    )
    (net (code "195") (name "UB") (class "Default")
      (node (ref "J9") (pin "P$2") (pinfunction "P$2_P$2") (pintype "bidirectional"))
      (node (ref "R109") (pin "P$2") (pinfunction "2_P$2") (pintype "passive"))
    )
    (net (code "196") (name "UC") (class "Default")
      (node (ref "C93") (pin "P$1") (pinfunction "P$1_P$1") (pintype "bidirectional"))
      (node (ref "J10") (pin "P$1") (pinfunction "P$1_P$1") (pintype "bidirectional"))
      (node (ref "R118") (pin "P$2") (pinfunction "2_P$2") (pintype "passive"))
      (node (ref "U$7") (pin "P$1") (pinfunction "P$1_P$1") (pintype "bidirectional"))
      (node (ref "U7") (pin "P$5") (pinfunction "AC_L_P$5") (pintype "bidirectional"))
    )
    (net (code "197") (name "USBHS_FAULT") (class "Default")
      (node (ref "R12") (pin "P$1") (pinfunction "1_P$1") (pintype "passive"))
      (node (ref "U2") (pin "3") (pinfunction "FLG_3") (pintype "input"))
      (node (ref "U4") (pin "78") (pinfunction "P3_8_78") (pintype "bidirectional"))
    )
    (net (code "198") (name "USBHS_N") (class "Default")
      (node (ref "J3") (pin "D-") (pinfunction "D-_D-") (pintype "bidirectional"))
      (node (ref "U4") (pin "31") (pinfunction "USBHS_DM_31") (pintype "bidirectional"))
    )
    (net (code "199") (name "USBHS_P") (class "Default")
      (node (ref "J3") (pin "D+") (pinfunction "D+_D+") (pintype "bidirectional"))
      (node (ref "U4") (pin "32") (pinfunction "USBHS_DP_32") (pintype "bidirectional"))
    )
    (net (code "200") (name "USBHS_VBUS") (class "Default")
      (node (ref "C11") (pin "P$1") (pinfunction "1_P$1") (pintype "passive"))
      (node (ref "C15") (pin "1") (pinfunction "1_1") (pintype "passive"))
      (node (ref "J3") (pin "VBUS") (pinfunction "VBUS_VBUS") (pintype "power_in"))
      (node (ref "U2") (pin "5") (pinfunction "OUT_5") (pintype "input"))
      (node (ref "U4") (pin "17") (pinfunction "PB_1_17") (pintype "bidirectional"))
    )
    (net (code "201") (name "USBHS_VBUSEN") (class "Default")
      (node (ref "R1") (pin "P$1") (pinfunction "1_P$1") (pintype "passive"))
      (node (ref "U2") (pin "1") (pinfunction "EN_1") (pintype "input"))
    )
    (net (code "202") (name "USB_N") (class "Default")
      (node (ref "R5") (pin "P$1") (pinfunction "1_P$1") (pintype "passive"))
      (node (ref "U4") (pin "46") (pinfunction "USB_DM_46") (pintype "bidirectional"))
    )
    (net (code "203") (name "USB_P") (class "Default")
      (node (ref "R6") (pin "P$1") (pinfunction "1_P$1") (pintype "passive"))
      (node (ref "U4") (pin "47") (pinfunction "USB_DP_47") (pintype "bidirectional"))
    )
    (net (code "204") (name "USB_VBUS_B") (class "Default")
      (node (ref "R4") (pin "P$1") (pinfunction "1_P$1") (pintype "passive"))
      (node (ref "U4") (pin "44") (pinfunction "P4_7_44") (pintype "bidirectional"))
    )
    (net (code "205") (name "VAN") (class "Default")
      (node (ref "C80") (pin "P$2") (pinfunction "2_P$2") (pintype "passive"))
      (node (ref "R108") (pin "P$1") (pinfunction "1_P$1") (pintype "passive"))
      (node (ref "U6") (pin "14") (pinfunction "V1N_14") (pintype "input"))
    )
    (net (code "206") (name "VAP") (class "Default")
      (node (ref "C79") (pin "P$2") (pinfunction "2_P$2") (pintype "passive"))
      (node (ref "R106") (pin "P$1") (pinfunction "1_P$1") (pintype "passive"))
      (node (ref "R107") (pin "P$1") (pinfunction "1_P$1") (pintype "passive"))
      (node (ref "U6") (pin "13") (pinfunction "V1P_13") (pintype "input"))
    )
    (net (code "207") (name "VBN") (class "Default")
      (node (ref "C82") (pin "P$2") (pinfunction "2_P$2") (pintype "passive"))
      (node (ref "R117") (pin "P$1") (pinfunction "1_P$1") (pintype "passive"))
      (node (ref "U6") (pin "16") (pinfunction "V2N_16") (pintype "input"))
    )
    (net (code "208") (name "VBP") (class "Default")
      (node (ref "C81") (pin "P$2") (pinfunction "2_P$2") (pintype "passive"))
      (node (ref "R115") (pin "P$1") (pinfunction "1_P$1") (pintype "passive"))
      (node (ref "R116") (pin "P$1") (pinfunction "1_P$1") (pintype "passive"))
      (node (ref "U6") (pin "15") (pinfunction "V2P_15") (pintype "input"))
    )
    (net (code "209") (name "VCC") (class "Default")
      (node (ref "C94") (pin "P$1") (pinfunction "1_P$1") (pintype "passive"))
      (node (ref "C95") (pin "P$1") (pinfunction "1_P$1") (pintype "passive"))
      (node (ref "C96") (pin "1") (pinfunction "1_1") (pintype "passive"))
      (node (ref "C97") (pin "P$1") (pinfunction "1_P$1") (pintype "passive"))
      (node (ref "IC3") (pin "1") (pinfunction "IN_1") (pintype "input"))
      (node (ref "IC4") (pin "1") (pinfunction "IN_1") (pintype "input"))
      (node (ref "U$8") (pin "P+") (pinfunction "+_P+") (pintype "passive"))
      (node (ref "U7") (pin "P$2") (pinfunction "VOUT+_P$2") (pintype "bidirectional"))
    )
    (net (code "210") (name "VCL_F(FLASH)") (class "Default")
      (node (ref "C36") (pin "P$2") (pinfunction "2_P$2") (pintype "passive"))
      (node (ref "U4") (pin "112") (pinfunction "VCL_F(FLASH)_112") (pintype "bidirectional"))
    )
    (net (code "211") (name "VCN") (class "Default")
      (node (ref "C84") (pin "P$2") (pinfunction "2_P$2") (pintype "passive"))
      (node (ref "R126") (pin "P$1") (pinfunction "1_P$1") (pintype "passive"))
      (node (ref "U6") (pin "18") (pinfunction "V3N_18") (pintype "input"))
    )
    (net (code "212") (name "VCP") (class "Default")
      (node (ref "C83") (pin "P$2") (pinfunction "2_P$2") (pintype "passive"))
      (node (ref "R124") (pin "P$1") (pinfunction "1_P$1") (pintype "passive"))
      (node (ref "R125") (pin "P$1") (pinfunction "1_P$1") (pintype "passive"))
      (node (ref "U6") (pin "17") (pinfunction "V3P_17") (pintype "input"))
    )
    (net (code "213") (name "VDD") (class "Default")
      (node (ref "C1") (pin "P$2") (pinfunction "2_P$2") (pintype "passive"))
      (node (ref "C10") (pin "P$2") (pinfunction "2_P$2") (pintype "passive"))
      (node (ref "C13") (pin "P$2") (pinfunction "2_P$2") (pintype "passive"))
      (node (ref "C14") (pin "P$2") (pinfunction "2_P$2") (pintype "passive"))
      (node (ref "C2") (pin "P$2") (pinfunction "2_P$2") (pintype "passive"))
      (node (ref "C30") (pin "P$2") (pinfunction "2_P$2") (pintype "passive"))
      (node (ref "C32") (pin "P$1") (pinfunction "1_P$1") (pintype "passive"))
      (node (ref "C48") (pin "1") (pinfunction "1_1") (pintype "passive"))
      (node (ref "C49") (pin "P$1") (pinfunction "1_P$1") (pintype "passive"))
      (node (ref "C54") (pin "P$2") (pinfunction "2_P$2") (pintype "passive"))
      (node (ref "C55") (pin "P$2") (pinfunction "2_P$2") (pintype "passive"))
      (node (ref "C56") (pin "P$2") (pinfunction "2_P$2") (pintype "passive"))
      (node (ref "C58") (pin "P$1") (pinfunction "1_P$1") (pintype "passive"))
      (node (ref "C59") (pin "P$1") (pinfunction "1_P$1") (pintype "passive"))
      (node (ref "C60") (pin "P$1") (pinfunction "1_P$1") (pintype "passive"))
      (node (ref "C61") (pin "P$2") (pinfunction "2_P$2") (pintype "passive"))
      (node (ref "C87") (pin "P$2") (pinfunction "2_P$2") (pintype "passive"))
      (node (ref "C88") (pin "P$2") (pinfunction "2_P$2") (pintype "passive"))
      (node (ref "C92") (pin "P$1") (pinfunction "1_P$1") (pintype "passive"))
      (node (ref "C98") (pin "P$1") (pinfunction "1_P$1") (pintype "passive"))
      (node (ref "C99") (pin "1") (pinfunction "1_1") (pintype "passive"))
      (node (ref "FB2/2") (pin "1") (pinfunction "P$1_1") (pintype "bidirectional"))
      (node (ref "IC4") (pin "3") (pinfunction "OUT_3") (pintype "output"))
      (node (ref "J11") (pin "2") (pinfunction "2_2") (pintype "passive"))
      (node (ref "J11") (pin "4") (pinfunction "4_4") (pintype "passive"))
      (node (ref "R127") (pin "P$2") (pinfunction "2_P$2") (pintype "passive"))
      (node (ref "R128") (pin "P$1") (pinfunction "1_P$1") (pintype "passive"))
      (node (ref "R18") (pin "P$2") (pinfunction "2_P$2") (pintype "passive"))
      (node (ref "R23") (pin "P$2") (pinfunction "2_P$2") (pintype "passive"))
      (node (ref "R24") (pin "P$2") (pinfunction "2_P$2") (pintype "passive"))
      (node (ref "R26") (pin "P$2") (pinfunction "2_P$2") (pintype "passive"))
      (node (ref "R27") (pin "P$2") (pinfunction "2_P$2") (pintype "passive"))
      (node (ref "R28") (pin "P$2") (pinfunction "2_P$2") (pintype "passive"))
      (node (ref "R29") (pin "P$2") (pinfunction "2_P$2") (pintype "passive"))
      (node (ref "U$1") (pin "P$1") (pinfunction "P$1_P$1") (pintype "bidirectional"))
      (node (ref "U3") (pin "14") (pinfunction "VDDIO_14") (pintype "power_in"))
      (node (ref "U4") (pin "110") (pinfunction "VCC(IO)5_110") (pintype "bidirectional"))
      (node (ref "U4") (pin "123") (pinfunction "VCC(IO)6_123") (pintype "bidirectional"))
      (node (ref "U4") (pin "138") (pinfunction "VCC(IO)7_138") (pintype "bidirectional"))
      (node (ref "U4") (pin "149") (pinfunction "VCC(IO)8_149") (pintype "bidirectional"))
      (node (ref "U4") (pin "154") (pinfunction "VREFH_154") (pintype "bidirectional"))
      (node (ref "U4") (pin "155") (pinfunction "AVCC0_155") (pintype "bidirectional"))
      (node (ref "U4") (pin "158") (pinfunction "VREFH0_158") (pintype "bidirectional"))
      (node (ref "U4") (pin "171") (pinfunction "VCC(IO)9_171") (pintype "bidirectional"))
      (node (ref "U4") (pin "25") (pinfunction "VCC1_25") (pintype "bidirectional"))
      (node (ref "U4") (pin "26") (pinfunction "AVCC_SUBHS_26") (pintype "bidirectional"))
      (node (ref "U4") (pin "34") (pinfunction "VCC_USBHS_34") (pintype "bidirectional"))
      (node (ref "U4") (pin "48") (pinfunction "VCC_USB_48") (pintype "bidirectional"))
      (node (ref "U4") (pin "61") (pinfunction "VCC(IO)2_61") (pintype "bidirectional"))
      (node (ref "U4") (pin "84") (pinfunction "VCC(IO)3_84") (pintype "bidirectional"))
      (node (ref "U4") (pin "97") (pinfunction "VCC(IO)4_97") (pintype "bidirectional"))
      (node (ref "U6") (pin "1") (pinfunction "AVDD_1") (pintype "power_in"))
      (node (ref "U6") (pin "48") (pinfunction "DVDD_48") (pintype "power_in"))
    )
    (net (code "214") (name "VDD1P8") (class "Default")
      (node (ref "C89") (pin "P$1") (pinfunction "1_P$1") (pintype "passive"))
      (node (ref "C90") (pin "P$1") (pinfunction "1_P$1") (pintype "passive"))
      (node (ref "U6") (pin "42") (pinfunction "VDD18_2_42") (pintype "power_in"))
      (node (ref "U6") (pin "43") (pinfunction "VDD18_43") (pintype "power_in"))
    )
    (net (code "215") (name "VDD5") (class "Default")
      (node (ref "C100") (pin "P$1") (pinfunction "1_P$1") (pintype "passive"))
      (node (ref "C101") (pin "1") (pinfunction "1_1") (pintype "passive"))
      (node (ref "C5") (pin "P$1") (pinfunction "1_P$1") (pintype "passive"))
      (node (ref "C8") (pin "P$1") (pinfunction "1_P$1") (pintype "passive"))
      (node (ref "IC3") (pin "3") (pinfunction "OUT_3") (pintype "output"))
      (node (ref "R1") (pin "P$2") (pinfunction "2_P$2") (pintype "passive"))
      (node (ref "R12") (pin "P$2") (pinfunction "2_P$2") (pintype "passive"))
      (node (ref "R129") (pin "P$1") (pinfunction "1_P$1") (pintype "passive"))
      (node (ref "U2") (pin "4") (pinfunction "VIN_4") (pintype "input"))
    )
    (net (code "216") (name "VDD_1.2") (class "Default")
      (node (ref "C45") (pin "P$1") (pinfunction "1_P$1") (pintype "passive"))
      (node (ref "C46") (pin "P$1") (pinfunction "1_P$1") (pintype "passive"))
      (node (ref "U3") (pin "1") (pinfunction "VDD_1.2_1") (pintype "power_in"))
    )
    (net (code "217") (name "VO") (class "Default")
      (node (ref "U$1") (pin "P$2") (pinfunction "P$2_P$2") (pintype "bidirectional"))
    )
    (net (code "218") (name "VREF") (class "Default")
      (node (ref "C85") (pin "P$1") (pinfunction "1_P$1") (pintype "passive"))
      (node (ref "C86") (pin "P$1") (pinfunction "1_P$1") (pintype "passive"))
      (node (ref "U6") (pin "11") (pinfunction "VREF_11") (pintype "output"))
    )
    (net (code "219") (name "WARNOUT") (class "Default")
      (node (ref "U4") (pin "128") (pinfunction "P1_4_128") (pintype "bidirectional"))
      (node (ref "U6") (pin "29") (pinfunction "WARNOUT_29") (pintype "output"))
    )
    (net (code "220") (name "WIFI_GP0") (class "Default")
      (node (ref "U$1") (pin "P$10") (pinfunction "P$10_P$10") (pintype "bidirectional"))
    )
    (net (code "221") (name "WIFI_RST") (class "Default")
      (node (ref "U$1") (pin "P$9") (pinfunction "P$9_P$9") (pintype "bidirectional"))
    )
    (net (code "222") (name "XCIN") (class "Default")
      (node (ref "C50") (pin "P$1") (pinfunction "1_P$1") (pintype "passive"))
      (node (ref "U4") (pin "20") (pinfunction "XCIN_20") (pintype "bidirectional"))
      (node (ref "X3") (pin "P$1") (pinfunction "P$1_P$1") (pintype "bidirectional"))
    )
    (net (code "223") (name "XCOUT") (class "Default")
      (node (ref "C51") (pin "P$1") (pinfunction "1_P$1") (pintype "passive"))
      (node (ref "U4") (pin "21") (pinfunction "XCOUT_21") (pintype "bidirectional"))
      (node (ref "X3") (pin "P$2") (pinfunction "P$2_P$2") (pintype "bidirectional"))
    )
    (net (code "224") (name "XII") (class "Default")
      (node (ref "C42") (pin "P$1") (pinfunction "1_P$1") (pintype "passive"))
      (node (ref "U$3") (pin "1") (pinfunction "1_1") (pintype "bidirectional"))
      (node (ref "U3") (pin "8") (pinfunction "XI_8") (pintype "input"))
    )
    (net (code "225") (name "XOO") (class "Default")
      (node (ref "C41") (pin "P$1") (pinfunction "1_P$1") (pintype "passive"))
      (node (ref "U$3") (pin "3") (pinfunction "3_3") (pintype "bidirectional"))
      (node (ref "U3") (pin "7") (pinfunction "XO_7") (pintype "output"))
    )
    (net (code "226") (name "XTAL1") (class "Default")
      (node (ref "C52") (pin "P$1") (pinfunction "1_P$1") (pintype "passive"))
      (node (ref "U4") (pin "23") (pinfunction "P2_13/XTAL_23") (pintype "bidirectional"))
      (node (ref "X4") (pin "1") (pinfunction "1_1") (pintype "bidirectional"))
    )
    (net (code "227") (name "XTAL2") (class "Default")
      (node (ref "C53") (pin "P$1") (pinfunction "1_P$1") (pintype "passive"))
      (node (ref "U4") (pin "24") (pinfunction "P2_12/EXTAL_24") (pintype "bidirectional"))
      (node (ref "X4") (pin "3") (pinfunction "3_3") (pintype "bidirectional"))
    )
    (net (code "228") (name "ZX0") (class "Default")
      (node (ref "U4") (pin "135") (pinfunction "P8_2_135") (pintype "bidirectional"))
      (node (ref "U6") (pin "22") (pinfunction "ZX0_22") (pintype "output"))
    )
    (net (code "229") (name "ZX1") (class "Default")
      (node (ref "U4") (pin "134") (pinfunction "P8_1_134") (pintype "bidirectional"))
      (node (ref "U6") (pin "23") (pinfunction "ZX1_23") (pintype "output"))
    )
    (net (code "230") (name "ZX2") (class "Default")
      (node (ref "U4") (pin "133") (pinfunction "P8_0_133") (pintype "bidirectional"))
      (node (ref "U6") (pin "24") (pinfunction "ZX2_24") (pintype "output"))
    )
    (net (code "231") (name "unconnected-(U4-VBAT-Pad18)") (class "Default")
      (node (ref "U4") (pin "18") (pinfunction "VBAT_18") (pintype "bidirectional"))
    )
    (net (code "232") (name "unconnected-(U6-NC-Pad46)") (class "Default")
      (node (ref "U6") (pin "46") (pinfunction "NC_46") (pintype "no_connect"))
    )
    (net (code "233") (name "unconnected-(U6-NC_2-Pad35)") (class "Default")
      (node (ref "U6") (pin "35") (pinfunction "NC_2_35") (pintype "no_connect"))
    )
    (net (code "234") (name "unconnected-(U6-NC_3-Pad45)") (class "Default")
      (node (ref "U6") (pin "45") (pinfunction "NC_3_45") (pintype "no_connect"))
    )
    (net (code "235") (name "unconnected-(U7-NC1-PadP$1)") (class "Default")
      (node (ref "U7") (pin "P$1") (pinfunction "NC1_P$1") (pintype "bidirectional"))
    )
    (net (code "236") (name "unconnected-(U7-NC2-PadP$4)") (class "Default")
      (node (ref "U7") (pin "P$4") (pinfunction "NC2_P$4") (pintype "bidirectional"))
    )
    (net (code "237") (name "unconnected-(U7-NC3-PadP$7)") (class "Default")
      (node (ref "U7") (pin "P$7") (pinfunction "NC3_P$7") (pintype "bidirectional"))
    )
  )
)
